# reaction_wheel_board.net
KiCad netlist of a schematic drawn in EAGLE
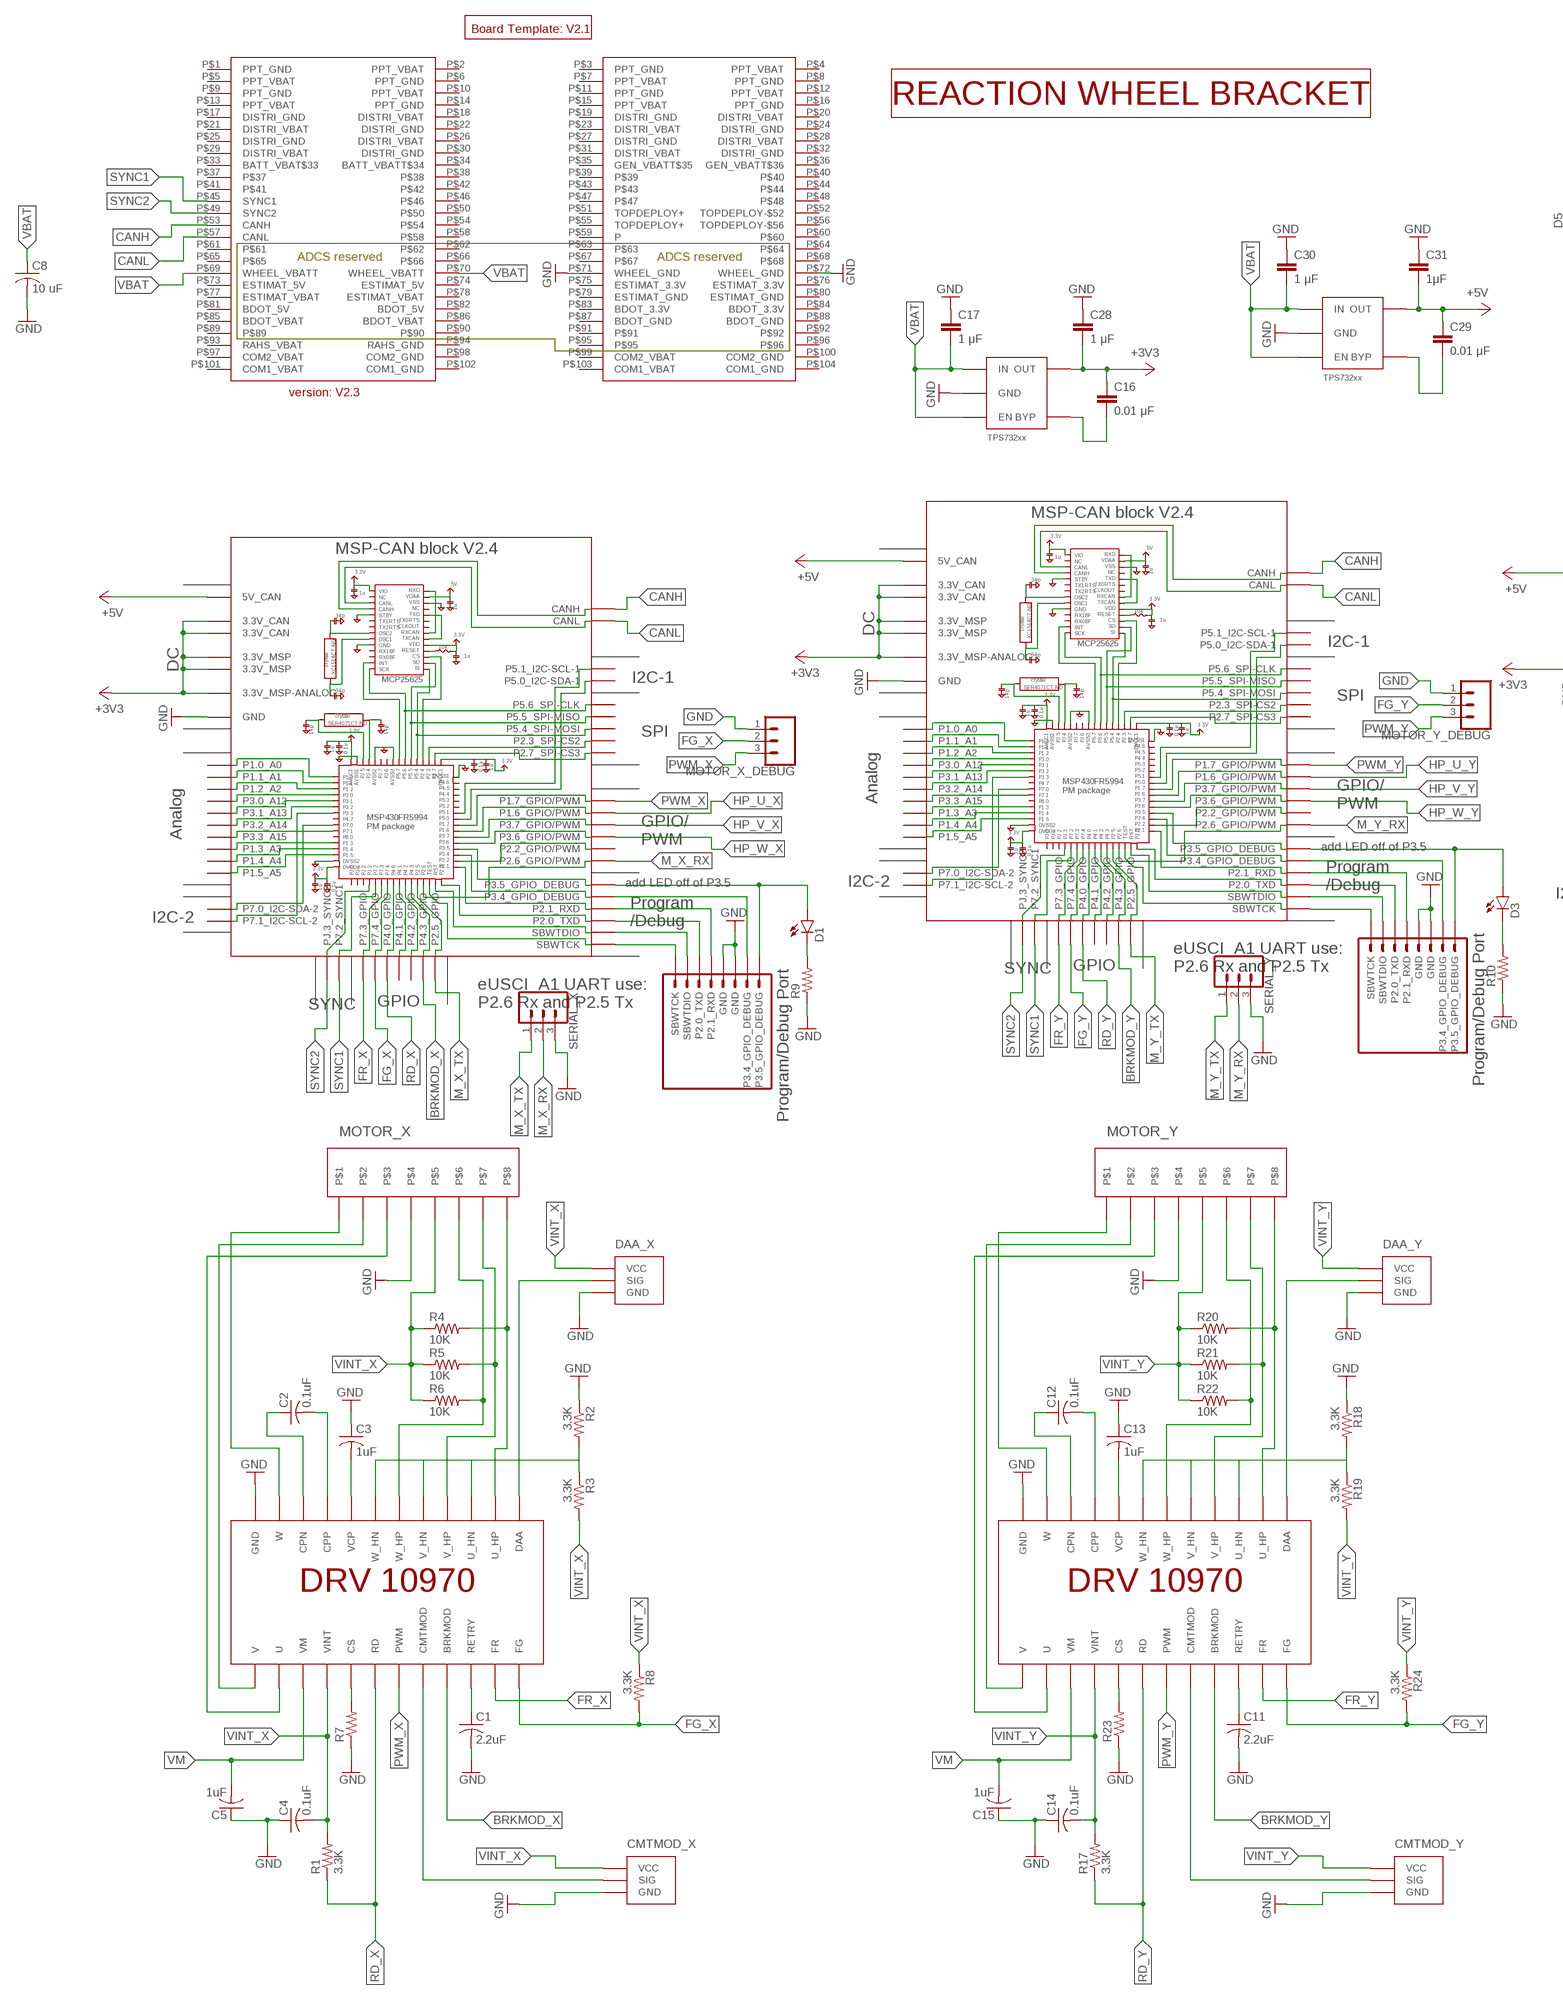
[diagram p0: schematic, sheet 1, part 1 of 2]
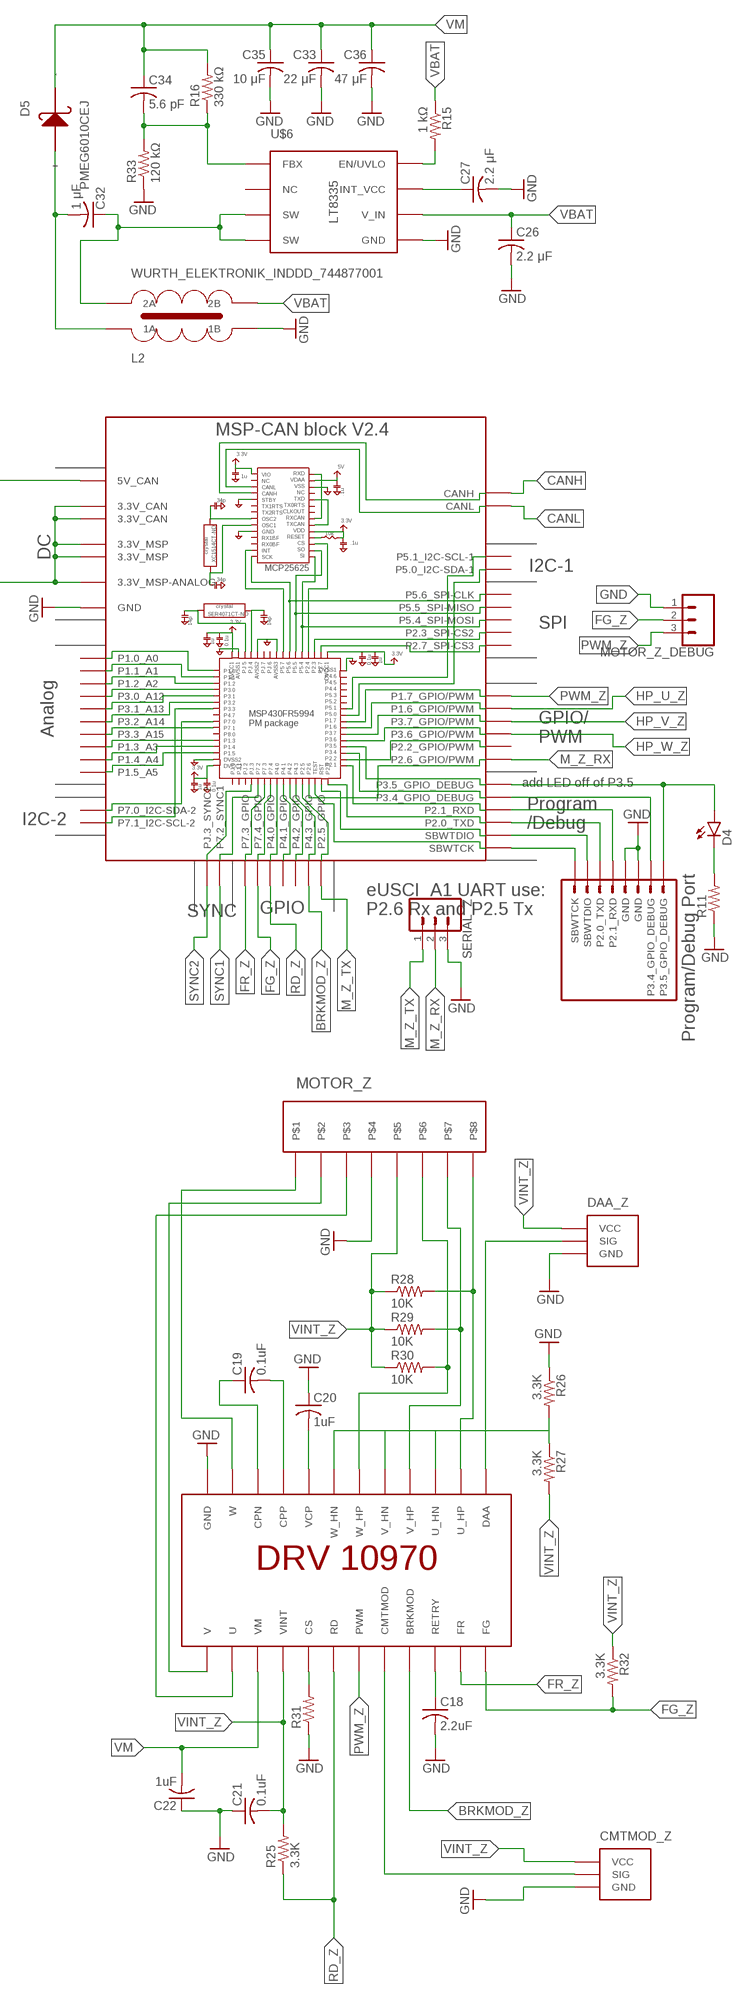
[diagram p1: schematic, sheet 1, part 2 of 2]

(export (version "E")
  (design (tool "Eeschema 10.0.6"))
  (components
    (comp (ref "C1")
      (value "2.2uF")
      (footprint "eagle-import:C1206")
      (libsource (lib "eagle-import") (part "C-USC1206"))
    )
    (comp (ref "C2")
      (value "0.1uF")
      (footprint "eagle-import:C0805")
      (libsource (lib "eagle-import") (part "C-USC0805"))
    )
    (comp (ref "C3")
      (value "1uF")
      (footprint "eagle-import:C1206")
      (libsource (lib "eagle-import") (part "C-USC1206"))
    )
    (comp (ref "C4")
      (value "0.1uF")
      (footprint "eagle-import:C0805")
      (libsource (lib "eagle-import") (part "C-USC0805"))
    )
    (comp (ref "C5")
      (value "1uF")
      (footprint "eagle-import:C1206")
      (libsource (lib "eagle-import") (part "C-USC1206"))
    )
    (comp (ref "C8")
      (value "10 uF")
      (footprint "eagle-import:C0805")
      (libsource (lib "eagle-import") (part "C-USC0805"))
    )
    (comp (ref "C11")
      (value "2.2uF")
      (footprint "eagle-import:C1206")
      (libsource (lib "eagle-import") (part "C-USC1206"))
    )
    (comp (ref "C12")
      (value "0.1uF")
      (footprint "eagle-import:C0805")
      (libsource (lib "eagle-import") (part "C-USC0805"))
    )
    (comp (ref "C13")
      (value "1uF")
      (footprint "eagle-import:C1206")
      (libsource (lib "eagle-import") (part "C-USC1206"))
    )
    (comp (ref "C14")
      (value "0.1uF")
      (footprint "eagle-import:C0805")
      (libsource (lib "eagle-import") (part "C-USC0805"))
    )
    (comp (ref "C15")
      (value "1uF")
      (footprint "eagle-import:C1206")
      (libsource (lib "eagle-import") (part "C-USC1206"))
    )
    (comp (ref "C16")
      (value "0.01 μF")
      (footprint "eagle-import:0805")
      (libsource (lib "eagle-import") (part "CAPACITOR0805"))
    )
    (comp (ref "C17")
      (value "1 μF")
      (footprint "eagle-import:0805")
      (libsource (lib "eagle-import") (part "CAPACITOR0805"))
    )
    (comp (ref "C18")
      (value "2.2uF")
      (footprint "eagle-import:C1206")
      (libsource (lib "eagle-import") (part "C-USC1206"))
    )
    (comp (ref "C19")
      (value "0.1uF")
      (footprint "eagle-import:C0805")
      (libsource (lib "eagle-import") (part "C-USC0805"))
    )
    (comp (ref "C20")
      (value "1uF")
      (footprint "eagle-import:C1206")
      (libsource (lib "eagle-import") (part "C-USC1206"))
    )
    (comp (ref "C21")
      (value "0.1uF")
      (footprint "eagle-import:C0805")
      (libsource (lib "eagle-import") (part "C-USC0805"))
    )
    (comp (ref "C22")
      (value "1uF")
      (footprint "eagle-import:C1206")
      (libsource (lib "eagle-import") (part "C-USC1206"))
    )
    (comp (ref "C26")
      (value "2.2 μF")
      (footprint "eagle-import:C0805")
      (libsource (lib "eagle-import") (part "C-USC0805"))
    )
    (comp (ref "C27")
      (value "2.2 μF")
      (footprint "eagle-import:C0805")
      (libsource (lib "eagle-import") (part "C-USC0805"))
    )
    (comp (ref "C28")
      (value "1 μF")
      (footprint "eagle-import:0805")
      (libsource (lib "eagle-import") (part "CAPACITOR0805"))
    )
    (comp (ref "C29")
      (value "0.01 μF")
      (footprint "eagle-import:0805")
      (libsource (lib "eagle-import") (part "CAPACITOR0805"))
    )
    (comp (ref "C30")
      (value "1 μF")
      (footprint "eagle-import:0805")
      (libsource (lib "eagle-import") (part "CAPACITOR0805"))
    )
    (comp (ref "C31")
      (value "1μF")
      (footprint "eagle-import:0805")
      (libsource (lib "eagle-import") (part "CAPACITOR0805"))
    )
    (comp (ref "C32")
      (value "1 μF")
      (footprint "eagle-import:C0805")
      (libsource (lib "eagle-import") (part "C-USC0805"))
    )
    (comp (ref "C33")
      (value "22 μF")
      (footprint "eagle-import:C1206")
      (libsource (lib "eagle-import") (part "C-USC1206"))
    )
    (comp (ref "C34")
      (value "5.6 pF")
      (footprint "eagle-import:C0805")
      (libsource (lib "eagle-import") (part "C-USC0805"))
    )
    (comp (ref "C35")
      (value "10 μF")
      (footprint "eagle-import:C0805")
      (libsource (lib "eagle-import") (part "C-USC0805"))
    )
    (comp (ref "C36")
      (value "47 μF")
      (footprint "eagle-import:C1206")
      (libsource (lib "eagle-import") (part "C-USC1206"))
    )
    (comp (ref "CMTMOD_X")
      (value "0_OHM_JUMPER")
      (footprint "eagle-import:0_OHM_JUMPER")
      (libsource (lib "eagle-import") (part "0_OHM_JUMPER"))
    )
    (comp (ref "CMTMOD_Y")
      (value "0_OHM_JUMPER")
      (footprint "eagle-import:0_OHM_JUMPER")
      (libsource (lib "eagle-import") (part "0_OHM_JUMPER"))
    )
    (comp (ref "CMTMOD_Z")
      (value "0_OHM_JUMPER")
      (footprint "eagle-import:0_OHM_JUMPER")
      (libsource (lib "eagle-import") (part "0_OHM_JUMPER"))
    )
    (comp (ref "D1")
      (value "LED")
      (footprint "eagle-import:LED-1206")
      (libsource (lib "eagle-import") (part "LED"))
    )
    (comp (ref "D3")
      (value "LED")
      (footprint "eagle-import:LED-1206")
      (libsource (lib "eagle-import") (part "LED"))
    )
    (comp (ref "D4")
      (value "LED")
      (footprint "eagle-import:LED-1206")
      (libsource (lib "eagle-import") (part "LED"))
    )
    (comp (ref "D5")
      (value "PMEG6010CEJ")
      (footprint "eagle-import:SC-90")
      (libsource (lib "eagle-import") (part "PMEG6010CEJ"))
    )
    (comp (ref "DAA_X")
      (value "0_OHM_JUMPER")
      (footprint "eagle-import:0_OHM_JUMPER")
      (libsource (lib "eagle-import") (part "0_OHM_JUMPER"))
    )
    (comp (ref "DAA_Y")
      (value "0_OHM_JUMPER")
      (footprint "eagle-import:0_OHM_JUMPER")
      (libsource (lib "eagle-import") (part "0_OHM_JUMPER"))
    )
    (comp (ref "DAA_Z")
      (value "0_OHM_JUMPER")
      (footprint "eagle-import:0_OHM_JUMPER")
      (libsource (lib "eagle-import") (part "0_OHM_JUMPER"))
    )
    (comp (ref "L2")
      (value "WURTH_ELEKTRONIK_INDDD_744877001")
      (footprint "eagle-import:WURTH_ELEKTRONIK_INDDD_744877001")
      (libsource (lib "eagle-import") (part "WURTH_ELEKTRONIK_INDDD_744877001"))
    )
    (comp (ref "MOTOR_X")
      (value "PICOLOCK_8")
      (footprint "eagle-import:PICOLOCK_8")
      (libsource (lib "eagle-import") (part "PICOLOCK_8"))
    )
    (comp (ref "MOTOR_X_DEBUG")
      (value "CONN_03LOCK")
      (footprint "eagle-import:1X03_LOCK")
      (libsource (lib "eagle-import") (part "CONN_03LOCK"))
    )
    (comp (ref "MOTOR_Y")
      (value "PICOLOCK_8")
      (footprint "eagle-import:PICOLOCK_8")
      (libsource (lib "eagle-import") (part "PICOLOCK_8"))
    )
    (comp (ref "MOTOR_Y_DEBUG")
      (value "CONN_03LOCK")
      (footprint "eagle-import:1X03_LOCK")
      (libsource (lib "eagle-import") (part "CONN_03LOCK"))
    )
    (comp (ref "MOTOR_Z")
      (value "PICOLOCK_8")
      (footprint "eagle-import:PICOLOCK_8")
      (libsource (lib "eagle-import") (part "PICOLOCK_8"))
    )
    (comp (ref "MOTOR_Z_DEBUG")
      (value "CONN_03LOCK")
      (footprint "eagle-import:1X03_LOCK")
      (libsource (lib "eagle-import") (part "CONN_03LOCK"))
    )
    (comp (ref "MSP_X_DEBUG")
      (value "PROGRAM/DEBUG_PORT")
      (footprint "eagle-import:1X08_CONNECTOR")
      (libsource (lib "eagle-import") (part "PROGRAM/DEBUG_PORT"))
    )
    (comp (ref "MSP_Y_DEBUG")
      (value "PROGRAM/DEBUG_PORT")
      (footprint "eagle-import:1X08_CONNECTOR")
      (libsource (lib "eagle-import") (part "PROGRAM/DEBUG_PORT"))
    )
    (comp (ref "MSP_Z_DEBUG")
      (value "PROGRAM/DEBUG_PORT")
      (footprint "eagle-import:1X08_CONNECTOR")
      (libsource (lib "eagle-import") (part "PROGRAM/DEBUG_PORT"))
    )
    (comp (ref "PC104")
      (value "PC104_CONNECTOR")
      (footprint "eagle-import:PC104_CONNECTOR")
      (libsource (lib "eagle-import") (part "PC104_CONNECTOR"))
    )
    (comp (ref "R1")
      (value "3.3K")
      (footprint "eagle-import:0805")
      (libsource (lib "eagle-import") (part "RESISTOR0805"))
    )
    (comp (ref "R2")
      (value "3.3K")
      (footprint "eagle-import:0805")
      (libsource (lib "eagle-import") (part "RESISTOR0805"))
    )
    (comp (ref "R3")
      (value "3.3K")
      (footprint "eagle-import:0805")
      (libsource (lib "eagle-import") (part "RESISTOR0805"))
    )
    (comp (ref "R4")
      (value "10K")
      (footprint "eagle-import:0805")
      (libsource (lib "eagle-import") (part "RESISTOR0805"))
    )
    (comp (ref "R5")
      (value "10K")
      (footprint "eagle-import:0805")
      (libsource (lib "eagle-import") (part "RESISTOR0805"))
    )
    (comp (ref "R6")
      (value "10K")
      (footprint "eagle-import:0805")
      (libsource (lib "eagle-import") (part "RESISTOR0805"))
    )
    (comp (ref "R7")
      (value "RESISTOR0805")
      (footprint "eagle-import:0805")
      (libsource (lib "eagle-import") (part "RESISTOR0805"))
    )
    (comp (ref "R8")
      (value "3.3K")
      (footprint "eagle-import:0805")
      (libsource (lib "eagle-import") (part "RESISTOR0805"))
    )
    (comp (ref "R9")
      (value "RESISTOR0805")
      (footprint "eagle-import:0805")
      (libsource (lib "eagle-import") (part "RESISTOR0805"))
    )
    (comp (ref "R10")
      (value "RESISTOR0805")
      (footprint "eagle-import:0805")
      (libsource (lib "eagle-import") (part "RESISTOR0805"))
    )
    (comp (ref "R11")
      (value "RESISTOR0805")
      (footprint "eagle-import:0805")
      (libsource (lib "eagle-import") (part "RESISTOR0805"))
    )
    (comp (ref "R15")
      (value "1 kΩ")
      (footprint "eagle-import:0805")
      (libsource (lib "eagle-import") (part "RESISTOR0805"))
    )
    (comp (ref "R16")
      (value "330 kΩ")
      (footprint "eagle-import:0805")
      (libsource (lib "eagle-import") (part "RESISTOR0805"))
    )
    (comp (ref "R17")
      (value "3.3K")
      (footprint "eagle-import:0805")
      (libsource (lib "eagle-import") (part "RESISTOR0805"))
    )
    (comp (ref "R18")
      (value "3.3K")
      (footprint "eagle-import:0805")
      (libsource (lib "eagle-import") (part "RESISTOR0805"))
    )
    (comp (ref "R19")
      (value "3.3K")
      (footprint "eagle-import:0805")
      (libsource (lib "eagle-import") (part "RESISTOR0805"))
    )
    (comp (ref "R20")
      (value "10K")
      (footprint "eagle-import:0805")
      (libsource (lib "eagle-import") (part "RESISTOR0805"))
    )
    (comp (ref "R21")
      (value "10K")
      (footprint "eagle-import:0805")
      (libsource (lib "eagle-import") (part "RESISTOR0805"))
    )
    (comp (ref "R22")
      (value "10K")
      (footprint "eagle-import:0805")
      (libsource (lib "eagle-import") (part "RESISTOR0805"))
    )
    (comp (ref "R23")
      (value "RESISTOR0805")
      (footprint "eagle-import:0805")
      (libsource (lib "eagle-import") (part "RESISTOR0805"))
    )
    (comp (ref "R24")
      (value "3.3K")
      (footprint "eagle-import:0805")
      (libsource (lib "eagle-import") (part "RESISTOR0805"))
    )
    (comp (ref "R25")
      (value "3.3K")
      (footprint "eagle-import:0805")
      (libsource (lib "eagle-import") (part "RESISTOR0805"))
    )
    (comp (ref "R26")
      (value "3.3K")
      (footprint "eagle-import:0805")
      (libsource (lib "eagle-import") (part "RESISTOR0805"))
    )
    (comp (ref "R27")
      (value "3.3K")
      (footprint "eagle-import:0805")
      (libsource (lib "eagle-import") (part "RESISTOR0805"))
    )
    (comp (ref "R28")
      (value "10K")
      (footprint "eagle-import:0805")
      (libsource (lib "eagle-import") (part "RESISTOR0805"))
    )
    (comp (ref "R29")
      (value "10K")
      (footprint "eagle-import:0805")
      (libsource (lib "eagle-import") (part "RESISTOR0805"))
    )
    (comp (ref "R30")
      (value "10K")
      (footprint "eagle-import:0805")
      (libsource (lib "eagle-import") (part "RESISTOR0805"))
    )
    (comp (ref "R31")
      (value "RESISTOR0805")
      (footprint "eagle-import:0805")
      (libsource (lib "eagle-import") (part "RESISTOR0805"))
    )
    (comp (ref "R32")
      (value "3.3K")
      (footprint "eagle-import:0805")
      (libsource (lib "eagle-import") (part "RESISTOR0805"))
    )
    (comp (ref "R33")
      (value "120 kΩ")
      (footprint "eagle-import:0805")
      (libsource (lib "eagle-import") (part "RESISTOR0805"))
    )
    (comp (ref "SERIAL_X")
      (value "CONN_03LOCK")
      (footprint "eagle-import:1X03_LOCK")
      (libsource (lib "eagle-import") (part "CONN_03LOCK"))
    )
    (comp (ref "SERIAL_Y")
      (value "CONN_03LOCK")
      (footprint "eagle-import:1X03_LOCK")
      (libsource (lib "eagle-import") (part "CONN_03LOCK"))
    )
    (comp (ref "SERIAL_Z")
      (value "CONN_03LOCK")
      (footprint "eagle-import:1X03_LOCK")
      (libsource (lib "eagle-import") (part "CONN_03LOCK"))
    )
    (comp (ref "U$1")
      (value "BOARD_TEMPLATESERCURED")
      (footprint "eagle-import:BOARD_TEMPLATE_SECURED")
      (libsource (lib "eagle-import") (part "BOARD_TEMPLATESERCURED"))
    )
    (comp (ref "U$3")
      (value "MSP-CAN_BLOCK")
      (footprint "eagle-import:MSP-CAN_BLOCK")
      (libsource (lib "eagle-import") (part "MSP-CAN_BLOCK"))
    )
    (comp (ref "U$6")
      (value "LT8335")
      (footprint "eagle-import:DDB")
      (libsource (lib "eagle-import") (part "LT8335"))
    )
    (comp (ref "U$7")
      (value "DRV10970")
      (footprint "eagle-import:DRV10970")
      (libsource (lib "eagle-import") (part "DRV10970"))
    )
    (comp (ref "U$9")
      (value "REACTION_WHEEL_BRACKET")
      (footprint "eagle-import:REACTION_WHEEL_BRACKET")
      (libsource (lib "eagle-import") (part "REACTION_WHEEL_BRACKET"))
    )
    (comp (ref "U$10")
      (value "MSP-CAN_BLOCK")
      (footprint "eagle-import:MSP-CAN_BLOCK")
      (libsource (lib "eagle-import") (part "MSP-CAN_BLOCK"))
    )
    (comp (ref "U$12")
      (value "DRV10970")
      (footprint "eagle-import:DRV10970")
      (libsource (lib "eagle-import") (part "DRV10970"))
    )
    (comp (ref "U$13")
      (value "MSP-CAN_BLOCK")
      (footprint "eagle-import:MSP-CAN_BLOCK")
      (libsource (lib "eagle-import") (part "MSP-CAN_BLOCK"))
    )
    (comp (ref "U$15")
      (value "DRV10970")
      (footprint "eagle-import:DRV10970")
      (libsource (lib "eagle-import") (part "DRV10970"))
    )
    (comp (ref "U2")
      (value "TPS732XX")
      (footprint "eagle-import:SOT-23-5")
      (libsource (lib "eagle-import") (part "TPS732XX"))
    )
    (comp (ref "U3")
      (value "TPS732XX")
      (footprint "eagle-import:SOT-23-5")
      (libsource (lib "eagle-import") (part "TPS732XX"))
    )
  )
  (nets
    (net (code "1") (name "+3V3") (class "Default")
      (node (ref "C16") (pin "1") (pinfunction "1_1") (pintype "passive"))
      (node (ref "C28") (pin "2") (pinfunction "2_2") (pintype "passive"))
      (node (ref "U$10") (pin "3.3V@CAN1") (pinfunction "3.3V_CAN_3.3V@CAN1") (pintype "bidirectional"))
      (node (ref "U$10") (pin "3.3V@CAN2") (pinfunction "3.3V_CAN_3.3V@CAN2") (pintype "bidirectional"))
      (node (ref "U$10") (pin "3.3V@MSP1") (pinfunction "3.3V_MSP_3.3V@MSP1") (pintype "bidirectional"))
      (node (ref "U$10") (pin "3.3V@MSP2") (pinfunction "3.3V_MSP_3.3V@MSP2") (pintype "bidirectional"))
      (node (ref "U$10") (pin "3.3V_ANALOG@MSP2") (pinfunction "3.3V_MSP-ANALOG_3.3V_ANALOG@MSP2") (pintype "bidirectional"))
      (node (ref "U$13") (pin "3.3V@CAN1") (pinfunction "3.3V_CAN_3.3V@CAN1") (pintype "bidirectional"))
      (node (ref "U$13") (pin "3.3V@CAN2") (pinfunction "3.3V_CAN_3.3V@CAN2") (pintype "bidirectional"))
      (node (ref "U$13") (pin "3.3V@MSP1") (pinfunction "3.3V_MSP_3.3V@MSP1") (pintype "bidirectional"))
      (node (ref "U$13") (pin "3.3V@MSP2") (pinfunction "3.3V_MSP_3.3V@MSP2") (pintype "bidirectional"))
      (node (ref "U$13") (pin "3.3V_ANALOG@MSP2") (pinfunction "3.3V_MSP-ANALOG_3.3V_ANALOG@MSP2") (pintype "bidirectional"))
      (node (ref "U$3") (pin "3.3V@CAN1") (pinfunction "3.3V_CAN_3.3V@CAN1") (pintype "bidirectional"))
      (node (ref "U$3") (pin "3.3V@CAN2") (pinfunction "3.3V_CAN_3.3V@CAN2") (pintype "bidirectional"))
      (node (ref "U$3") (pin "3.3V@MSP1") (pinfunction "3.3V_MSP_3.3V@MSP1") (pintype "bidirectional"))
      (node (ref "U$3") (pin "3.3V@MSP2") (pinfunction "3.3V_MSP_3.3V@MSP2") (pintype "bidirectional"))
      (node (ref "U$3") (pin "3.3V_ANALOG@MSP2") (pinfunction "3.3V_MSP-ANALOG_3.3V_ANALOG@MSP2") (pintype "bidirectional"))
      (node (ref "U2") (pin "P$5") (pinfunction "OUT_P$5") (pintype "bidirectional"))
    )
    (net (code "2") (name "+5V") (class "Default")
      (node (ref "C29") (pin "1") (pinfunction "1_1") (pintype "passive"))
      (node (ref "C31") (pin "2") (pinfunction "2_2") (pintype "passive"))
      (node (ref "U$10") (pin "5V") (pinfunction "5V_CAN_5V") (pintype "bidirectional"))
      (node (ref "U$13") (pin "5V") (pinfunction "5V_CAN_5V") (pintype "bidirectional"))
      (node (ref "U$3") (pin "5V") (pinfunction "5V_CAN_5V") (pintype "bidirectional"))
      (node (ref "U3") (pin "P$5") (pinfunction "OUT_P$5") (pintype "bidirectional"))
    )
    (net (code "3") (name "BRKMOD_X") (class "Default")
      (node (ref "U$3") (pin "P4.3_GPIO") (pinfunction "P4.3_GPIO_P4.3_GPIO") (pintype "bidirectional"))
      (node (ref "U$7") (pin "BRKMOD") (pinfunction "BRKMOD_BRKMOD") (pintype "bidirectional"))
    )
    (net (code "4") (name "BRKMOD_Y") (class "Default")
      (node (ref "U$10") (pin "P4.3_GPIO") (pinfunction "P4.3_GPIO_P4.3_GPIO") (pintype "bidirectional"))
      (node (ref "U$12") (pin "BRKMOD") (pinfunction "BRKMOD_BRKMOD") (pintype "bidirectional"))
    )
    (net (code "5") (name "BRKMOD_Z") (class "Default")
      (node (ref "U$13") (pin "P4.3_GPIO") (pinfunction "P4.3_GPIO_P4.3_GPIO") (pintype "bidirectional"))
      (node (ref "U$15") (pin "BRKMOD") (pinfunction "BRKMOD_BRKMOD") (pintype "bidirectional"))
    )
    (net (code "6") (name "CANH") (class "Default")
      (node (ref "PC104") (pin "P$53") (pinfunction "CANH_P$53") (pintype "bidirectional"))
      (node (ref "U$10") (pin "CANH") (pinfunction "CANH_CANH") (pintype "bidirectional"))
      (node (ref "U$13") (pin "CANH") (pinfunction "CANH_CANH") (pintype "bidirectional"))
      (node (ref "U$3") (pin "CANH") (pinfunction "CANH_CANH") (pintype "bidirectional"))
    )
    (net (code "7") (name "CANL") (class "Default")
      (node (ref "PC104") (pin "P$57") (pinfunction "CANL_P$57") (pintype "bidirectional"))
      (node (ref "U$10") (pin "CANL") (pinfunction "CANL_CANL") (pintype "bidirectional"))
      (node (ref "U$13") (pin "CANL") (pinfunction "CANL_CANL") (pintype "bidirectional"))
      (node (ref "U$3") (pin "CANL") (pinfunction "CANL_CANL") (pintype "bidirectional"))
    )
    (net (code "8") (name "FG_X") (class "Default")
      (node (ref "MOTOR_X_DEBUG") (pin "2") (pinfunction "2_2") (pintype "passive"))
      (node (ref "R8") (pin "2") (pinfunction "2_2") (pintype "passive"))
      (node (ref "U$3") (pin "P7.4_GPIO") (pinfunction "P7.4_GPIO_P7.4_GPIO") (pintype "bidirectional"))
      (node (ref "U$7") (pin "FG") (pinfunction "FG_FG") (pintype "bidirectional"))
    )
    (net (code "9") (name "FG_Y") (class "Default")
      (node (ref "MOTOR_Y_DEBUG") (pin "2") (pinfunction "2_2") (pintype "passive"))
      (node (ref "R24") (pin "2") (pinfunction "2_2") (pintype "passive"))
      (node (ref "U$10") (pin "P7.4_GPIO") (pinfunction "P7.4_GPIO_P7.4_GPIO") (pintype "bidirectional"))
      (node (ref "U$12") (pin "FG") (pinfunction "FG_FG") (pintype "bidirectional"))
    )
    (net (code "10") (name "FG_Z") (class "Default")
      (node (ref "MOTOR_Z_DEBUG") (pin "2") (pinfunction "2_2") (pintype "passive"))
      (node (ref "R32") (pin "2") (pinfunction "2_2") (pintype "passive"))
      (node (ref "U$13") (pin "P7.4_GPIO") (pinfunction "P7.4_GPIO_P7.4_GPIO") (pintype "bidirectional"))
      (node (ref "U$15") (pin "FG") (pinfunction "FG_FG") (pintype "bidirectional"))
    )
    (net (code "11") (name "FR_X") (class "Default")
      (node (ref "U$3") (pin "P7.3_GPIO") (pinfunction "P7.3_GPIO_P7.3_GPIO") (pintype "bidirectional"))
      (node (ref "U$7") (pin "FR") (pinfunction "FR_FR") (pintype "bidirectional"))
    )
    (net (code "12") (name "FR_Y") (class "Default")
      (node (ref "U$10") (pin "P7.3_GPIO") (pinfunction "P7.3_GPIO_P7.3_GPIO") (pintype "bidirectional"))
      (node (ref "U$12") (pin "FR") (pinfunction "FR_FR") (pintype "bidirectional"))
    )
    (net (code "13") (name "FR_Z") (class "Default")
      (node (ref "U$13") (pin "P7.3_GPIO") (pinfunction "P7.3_GPIO_P7.3_GPIO") (pintype "bidirectional"))
      (node (ref "U$15") (pin "FR") (pinfunction "FR_FR") (pintype "bidirectional"))
    )
    (net (code "14") (name "GND") (class "Default")
      (node (ref "C1") (pin "2") (pinfunction "2_2") (pintype "passive"))
      (node (ref "C11") (pin "2") (pinfunction "2_2") (pintype "passive"))
      (node (ref "C13") (pin "1") (pinfunction "1_1") (pintype "passive"))
      (node (ref "C14") (pin "1") (pinfunction "1_1") (pintype "passive"))
      (node (ref "C15") (pin "1") (pinfunction "1_1") (pintype "passive"))
      (node (ref "C17") (pin "1") (pinfunction "1_1") (pintype "passive"))
      (node (ref "C18") (pin "2") (pinfunction "2_2") (pintype "passive"))
      (node (ref "C20") (pin "1") (pinfunction "1_1") (pintype "passive"))
      (node (ref "C21") (pin "1") (pinfunction "1_1") (pintype "passive"))
      (node (ref "C22") (pin "1") (pinfunction "1_1") (pintype "passive"))
      (node (ref "C26") (pin "2") (pinfunction "2_2") (pintype "passive"))
      (node (ref "C27") (pin "2") (pinfunction "2_2") (pintype "passive"))
      (node (ref "C28") (pin "1") (pinfunction "1_1") (pintype "passive"))
      (node (ref "C3") (pin "1") (pinfunction "1_1") (pintype "passive"))
      (node (ref "C30") (pin "1") (pinfunction "1_1") (pintype "passive"))
      (node (ref "C31") (pin "1") (pinfunction "1_1") (pintype "passive"))
      (node (ref "C33") (pin "2") (pinfunction "2_2") (pintype "passive"))
      (node (ref "C35") (pin "2") (pinfunction "2_2") (pintype "passive"))
      (node (ref "C36") (pin "2") (pinfunction "2_2") (pintype "passive"))
      (node (ref "C4") (pin "1") (pinfunction "1_1") (pintype "passive"))
      (node (ref "C5") (pin "1") (pinfunction "1_1") (pintype "passive"))
      (node (ref "C8") (pin "2") (pinfunction "2_2") (pintype "passive"))
      (node (ref "CMTMOD_X") (pin "P$1") (pinfunction "GND_P$1") (pintype "bidirectional"))
      (node (ref "CMTMOD_Y") (pin "P$1") (pinfunction "GND_P$1") (pintype "bidirectional"))
      (node (ref "CMTMOD_Z") (pin "P$1") (pinfunction "GND_P$1") (pintype "bidirectional"))
      (node (ref "DAA_X") (pin "P$1") (pinfunction "GND_P$1") (pintype "bidirectional"))
      (node (ref "DAA_Y") (pin "P$1") (pinfunction "GND_P$1") (pintype "bidirectional"))
      (node (ref "DAA_Z") (pin "P$1") (pinfunction "GND_P$1") (pintype "bidirectional"))
      (node (ref "L2") (pin "P$2") (pinfunction "1B_P$2") (pintype "bidirectional"))
      (node (ref "MOTOR_X") (pin "P$4") (pinfunction "P$4_P$4") (pintype "bidirectional"))
      (node (ref "MOTOR_X_DEBUG") (pin "1") (pinfunction "1_1") (pintype "passive"))
      (node (ref "MOTOR_Y") (pin "P$4") (pinfunction "P$4_P$4") (pintype "bidirectional"))
      (node (ref "MOTOR_Y_DEBUG") (pin "1") (pinfunction "1_1") (pintype "passive"))
      (node (ref "MOTOR_Z") (pin "P$4") (pinfunction "P$4_P$4") (pintype "bidirectional"))
      (node (ref "MOTOR_Z_DEBUG") (pin "1") (pinfunction "1_1") (pintype "passive"))
      (node (ref "MSP_X_DEBUG") (pin "5") (pinfunction "GND_5") (pintype "bidirectional"))
      (node (ref "MSP_X_DEBUG") (pin "6") (pinfunction "GND_6") (pintype "bidirectional"))
      (node (ref "MSP_Y_DEBUG") (pin "5") (pinfunction "GND_5") (pintype "bidirectional"))
      (node (ref "MSP_Y_DEBUG") (pin "6") (pinfunction "GND_6") (pintype "bidirectional"))
      (node (ref "MSP_Z_DEBUG") (pin "5") (pinfunction "GND_5") (pintype "bidirectional"))
      (node (ref "MSP_Z_DEBUG") (pin "6") (pinfunction "GND_6") (pintype "bidirectional"))
      (node (ref "PC104") (pin "P$71") (pinfunction "WHEEL_GND_P$71") (pintype "bidirectional"))
      (node (ref "PC104") (pin "P$72") (pinfunction "WHEEL_GND_P$72") (pintype "bidirectional"))
      (node (ref "R10") (pin "1") (pinfunction "1_1") (pintype "passive"))
      (node (ref "R11") (pin "1") (pinfunction "1_1") (pintype "passive"))
      (node (ref "R18") (pin "1") (pinfunction "1_1") (pintype "passive"))
      (node (ref "R2") (pin "1") (pinfunction "1_1") (pintype "passive"))
      (node (ref "R23") (pin "1") (pinfunction "1_1") (pintype "passive"))
      (node (ref "R26") (pin "1") (pinfunction "1_1") (pintype "passive"))
      (node (ref "R31") (pin "1") (pinfunction "1_1") (pintype "passive"))
      (node (ref "R33") (pin "1") (pinfunction "1_1") (pintype "passive"))
      (node (ref "R7") (pin "1") (pinfunction "1_1") (pintype "passive"))
      (node (ref "R9") (pin "1") (pinfunction "1_1") (pintype "passive"))
      (node (ref "SERIAL_X") (pin "3") (pinfunction "3_3") (pintype "passive"))
      (node (ref "SERIAL_Y") (pin "3") (pinfunction "3_3") (pintype "passive"))
      (node (ref "SERIAL_Z") (pin "3") (pinfunction "3_3") (pintype "passive"))
      (node (ref "U$10") (pin "GND@1") (pinfunction "GND_GND@1") (pintype "bidirectional"))
      (node (ref "U$10") (pin "GND@10") (pinfunction "GND_GND@10") (pintype "bidirectional"))
      (node (ref "U$10") (pin "GND@11") (pinfunction "GND_GND@11") (pintype "bidirectional"))
      (node (ref "U$10") (pin "GND@12") (pinfunction "GND_GND@12") (pintype "bidirectional"))
      (node (ref "U$10") (pin "GND@13") (pinfunction "GND_GND@13") (pintype "bidirectional"))
      (node (ref "U$10") (pin "GND@14") (pinfunction "GND_GND@14") (pintype "bidirectional"))
      (node (ref "U$10") (pin "GND@15") (pinfunction "GND_GND@15") (pintype "bidirectional"))
      (node (ref "U$10") (pin "GND@16") (pinfunction "GND_GND@16") (pintype "bidirectional"))
      (node (ref "U$10") (pin "GND@17") (pinfunction "GND_GND@17") (pintype "bidirectional"))
      (node (ref "U$10") (pin "GND@2") (pinfunction "GND_GND@2") (pintype "bidirectional"))
      (node (ref "U$10") (pin "GND@26") (pinfunction "GND_GND@26") (pintype "bidirectional"))
      (node (ref "U$10") (pin "GND@3") (pinfunction "GND_GND@3") (pintype "bidirectional"))
      (node (ref "U$10") (pin "GND@4") (pinfunction "GND_GND@4") (pintype "bidirectional"))
      (node (ref "U$10") (pin "GND@5") (pinfunction "GND_GND@5") (pintype "bidirectional"))
      (node (ref "U$10") (pin "GND@7") (pinfunction "GND_GND@7") (pintype "bidirectional"))
      (node (ref "U$10") (pin "GND@8") (pinfunction "GND_GND@8") (pintype "bidirectional"))
      (node (ref "U$10") (pin "GND@9") (pinfunction "GND_GND@9") (pintype "bidirectional"))
      (node (ref "U$12") (pin "GND@1") (pinfunction "GND_GND@1") (pintype "bidirectional"))
      (node (ref "U$12") (pin "GND@2") (pinfunction "GND_GND@2") (pintype "bidirectional"))
      (node (ref "U$13") (pin "GND@1") (pinfunction "GND_GND@1") (pintype "bidirectional"))
      (node (ref "U$13") (pin "GND@10") (pinfunction "GND_GND@10") (pintype "bidirectional"))
      (node (ref "U$13") (pin "GND@11") (pinfunction "GND_GND@11") (pintype "bidirectional"))
      (node (ref "U$13") (pin "GND@12") (pinfunction "GND_GND@12") (pintype "bidirectional"))
      (node (ref "U$13") (pin "GND@13") (pinfunction "GND_GND@13") (pintype "bidirectional"))
      (node (ref "U$13") (pin "GND@14") (pinfunction "GND_GND@14") (pintype "bidirectional"))
      (node (ref "U$13") (pin "GND@15") (pinfunction "GND_GND@15") (pintype "bidirectional"))
      (node (ref "U$13") (pin "GND@16") (pinfunction "GND_GND@16") (pintype "bidirectional"))
      (node (ref "U$13") (pin "GND@17") (pinfunction "GND_GND@17") (pintype "bidirectional"))
      (node (ref "U$13") (pin "GND@2") (pinfunction "GND_GND@2") (pintype "bidirectional"))
      (node (ref "U$13") (pin "GND@26") (pinfunction "GND_GND@26") (pintype "bidirectional"))
      (node (ref "U$13") (pin "GND@3") (pinfunction "GND_GND@3") (pintype "bidirectional"))
      (node (ref "U$13") (pin "GND@4") (pinfunction "GND_GND@4") (pintype "bidirectional"))
      (node (ref "U$13") (pin "GND@5") (pinfunction "GND_GND@5") (pintype "bidirectional"))
      (node (ref "U$13") (pin "GND@7") (pinfunction "GND_GND@7") (pintype "bidirectional"))
      (node (ref "U$13") (pin "GND@8") (pinfunction "GND_GND@8") (pintype "bidirectional"))
      (node (ref "U$13") (pin "GND@9") (pinfunction "GND_GND@9") (pintype "bidirectional"))
      (node (ref "U$15") (pin "GND@1") (pinfunction "GND_GND@1") (pintype "bidirectional"))
      (node (ref "U$15") (pin "GND@2") (pinfunction "GND_GND@2") (pintype "bidirectional"))
      (node (ref "U$3") (pin "GND@1") (pinfunction "GND_GND@1") (pintype "bidirectional"))
      (node (ref "U$3") (pin "GND@10") (pinfunction "GND_GND@10") (pintype "bidirectional"))
      (node (ref "U$3") (pin "GND@11") (pinfunction "GND_GND@11") (pintype "bidirectional"))
      (node (ref "U$3") (pin "GND@12") (pinfunction "GND_GND@12") (pintype "bidirectional"))
      (node (ref "U$3") (pin "GND@13") (pinfunction "GND_GND@13") (pintype "bidirectional"))
      (node (ref "U$3") (pin "GND@14") (pinfunction "GND_GND@14") (pintype "bidirectional"))
      (node (ref "U$3") (pin "GND@15") (pinfunction "GND_GND@15") (pintype "bidirectional"))
      (node (ref "U$3") (pin "GND@16") (pinfunction "GND_GND@16") (pintype "bidirectional"))
      (node (ref "U$3") (pin "GND@17") (pinfunction "GND_GND@17") (pintype "bidirectional"))
      (node (ref "U$3") (pin "GND@2") (pinfunction "GND_GND@2") (pintype "bidirectional"))
      (node (ref "U$3") (pin "GND@26") (pinfunction "GND_GND@26") (pintype "bidirectional"))
      (node (ref "U$3") (pin "GND@3") (pinfunction "GND_GND@3") (pintype "bidirectional"))
      (node (ref "U$3") (pin "GND@4") (pinfunction "GND_GND@4") (pintype "bidirectional"))
      (node (ref "U$3") (pin "GND@5") (pinfunction "GND_GND@5") (pintype "bidirectional"))
      (node (ref "U$3") (pin "GND@7") (pinfunction "GND_GND@7") (pintype "bidirectional"))
      (node (ref "U$3") (pin "GND@8") (pinfunction "GND_GND@8") (pintype "bidirectional"))
      (node (ref "U$3") (pin "GND@9") (pinfunction "GND_GND@9") (pintype "bidirectional"))
      (node (ref "U$6") (pin "GND") (pinfunction "GND_GND") (pintype "bidirectional"))
      (node (ref "U$6") (pin "P$5") (pinfunction "GND_P$5") (pintype "bidirectional"))
      (node (ref "U$7") (pin "GND@1") (pinfunction "GND_GND@1") (pintype "bidirectional"))
      (node (ref "U$7") (pin "GND@2") (pinfunction "GND_GND@2") (pintype "bidirectional"))
      (node (ref "U2") (pin "P$2") (pinfunction "GND_P$2") (pintype "bidirectional"))
      (node (ref "U3") (pin "P$2") (pinfunction "GND_P$2") (pintype "bidirectional"))
    )
    (net (code "15") (name "HP_U_X") (class "Default")
      (node (ref "MOTOR_X") (pin "P$8") (pinfunction "P$8_P$8") (pintype "bidirectional"))
      (node (ref "R4") (pin "2") (pinfunction "2_2") (pintype "passive"))
      (node (ref "U$3") (pin "P1.6_GPIO/PWM") (pinfunction "P1.6_GPIO/PWM_P1.6_GPIO/PWM") (pintype "bidirectional"))
      (node (ref "U$7") (pin "U_HP") (pinfunction "U_HP_U_HP") (pintype "bidirectional"))
    )
    (net (code "16") (name "HP_U_Y") (class "Default")
      (node (ref "MOTOR_Y") (pin "P$8") (pinfunction "P$8_P$8") (pintype "bidirectional"))
      (node (ref "R20") (pin "2") (pinfunction "2_2") (pintype "passive"))
      (node (ref "U$10") (pin "P1.6_GPIO/PWM") (pinfunction "P1.6_GPIO/PWM_P1.6_GPIO/PWM") (pintype "bidirectional"))
      (node (ref "U$12") (pin "U_HP") (pinfunction "U_HP_U_HP") (pintype "bidirectional"))
    )
    (net (code "17") (name "HP_U_Z") (class "Default")
      (node (ref "MOTOR_Z") (pin "P$8") (pinfunction "P$8_P$8") (pintype "bidirectional"))
      (node (ref "R28") (pin "2") (pinfunction "2_2") (pintype "passive"))
      (node (ref "U$13") (pin "P1.6_GPIO/PWM") (pinfunction "P1.6_GPIO/PWM_P1.6_GPIO/PWM") (pintype "bidirectional"))
      (node (ref "U$15") (pin "U_HP") (pinfunction "U_HP_U_HP") (pintype "bidirectional"))
    )
    (net (code "18") (name "HP_V_X") (class "Default")
      (node (ref "MOTOR_X") (pin "P$7") (pinfunction "P$7_P$7") (pintype "bidirectional"))
      (node (ref "R5") (pin "2") (pinfunction "2_2") (pintype "passive"))
      (node (ref "U$3") (pin "P3.7_GPIO/PWM") (pinfunction "P3.7_GPIO/PWM_P3.7_GPIO/PWM") (pintype "bidirectional"))
      (node (ref "U$7") (pin "V_HP") (pinfunction "V_HP_V_HP") (pintype "bidirectional"))
    )
    (net (code "19") (name "HP_V_Y") (class "Default")
      (node (ref "MOTOR_Y") (pin "P$7") (pinfunction "P$7_P$7") (pintype "bidirectional"))
      (node (ref "R21") (pin "2") (pinfunction "2_2") (pintype "passive"))
      (node (ref "U$10") (pin "P3.7_GPIO/PWM") (pinfunction "P3.7_GPIO/PWM_P3.7_GPIO/PWM") (pintype "bidirectional"))
      (node (ref "U$12") (pin "V_HP") (pinfunction "V_HP_V_HP") (pintype "bidirectional"))
    )
    (net (code "20") (name "HP_V_Z") (class "Default")
      (node (ref "MOTOR_Z") (pin "P$7") (pinfunction "P$7_P$7") (pintype "bidirectional"))
      (node (ref "R29") (pin "2") (pinfunction "2_2") (pintype "passive"))
      (node (ref "U$13") (pin "P3.7_GPIO/PWM") (pinfunction "P3.7_GPIO/PWM_P3.7_GPIO/PWM") (pintype "bidirectional"))
      (node (ref "U$15") (pin "V_HP") (pinfunction "V_HP_V_HP") (pintype "bidirectional"))
    )
    (net (code "21") (name "HP_W_X") (class "Default")
      (node (ref "MOTOR_X") (pin "P$6") (pinfunction "P$6_P$6") (pintype "bidirectional"))
      (node (ref "R6") (pin "2") (pinfunction "2_2") (pintype "passive"))
      (node (ref "U$3") (pin "P3.6_GPIO/PWM") (pinfunction "P3.6_GPIO/PWM_P3.6_GPIO/PWM") (pintype "bidirectional"))
      (node (ref "U$7") (pin "W_HP") (pinfunction "W_HP_W_HP") (pintype "bidirectional"))
    )
    (net (code "22") (name "HP_W_Y") (class "Default")
      (node (ref "MOTOR_Y") (pin "P$6") (pinfunction "P$6_P$6") (pintype "bidirectional"))
      (node (ref "R22") (pin "2") (pinfunction "2_2") (pintype "passive"))
      (node (ref "U$10") (pin "P3.6_GPIO/PWM") (pinfunction "P3.6_GPIO/PWM_P3.6_GPIO/PWM") (pintype "bidirectional"))
      (node (ref "U$12") (pin "W_HP") (pinfunction "W_HP_W_HP") (pintype "bidirectional"))
    )
    (net (code "23") (name "HP_W_Z") (class "Default")
      (node (ref "MOTOR_Z") (pin "P$6") (pinfunction "P$6_P$6") (pintype "bidirectional"))
      (node (ref "R30") (pin "2") (pinfunction "2_2") (pintype "passive"))
      (node (ref "U$13") (pin "P3.6_GPIO/PWM") (pinfunction "P3.6_GPIO/PWM_P3.6_GPIO/PWM") (pintype "bidirectional"))
      (node (ref "U$15") (pin "W_HP") (pinfunction "W_HP_W_HP") (pintype "bidirectional"))
    )
    (net (code "24") (name "M_X_RX") (class "Default")
      (node (ref "SERIAL_X") (pin "2") (pinfunction "2_2") (pintype "passive"))
      (node (ref "U$3") (pin "P2.6_GPIO/PWM") (pinfunction "P2.6_GPIO/PWM_P2.6_GPIO/PWM") (pintype "bidirectional"))
    )
    (net (code "25") (name "M_X_TX") (class "Default")
      (node (ref "SERIAL_X") (pin "1") (pinfunction "1_1") (pintype "passive"))
      (node (ref "U$3") (pin "P2.5_GPIO") (pinfunction "P2.5_GPIO_P2.5_GPIO") (pintype "bidirectional"))
    )
    (net (code "26") (name "M_Y_RX") (class "Default")
      (node (ref "SERIAL_Y") (pin "2") (pinfunction "2_2") (pintype "passive"))
      (node (ref "U$10") (pin "P2.6_GPIO/PWM") (pinfunction "P2.6_GPIO/PWM_P2.6_GPIO/PWM") (pintype "bidirectional"))
    )
    (net (code "27") (name "M_Y_TX") (class "Default")
      (node (ref "SERIAL_Y") (pin "1") (pinfunction "1_1") (pintype "passive"))
      (node (ref "U$10") (pin "P2.5_GPIO") (pinfunction "P2.5_GPIO_P2.5_GPIO") (pintype "bidirectional"))
    )
    (net (code "28") (name "M_Z_RX") (class "Default")
      (node (ref "SERIAL_Z") (pin "2") (pinfunction "2_2") (pintype "passive"))
      (node (ref "U$13") (pin "P2.6_GPIO/PWM") (pinfunction "P2.6_GPIO/PWM_P2.6_GPIO/PWM") (pintype "bidirectional"))
    )
    (net (code "29") (name "M_Z_TX") (class "Default")
      (node (ref "SERIAL_Z") (pin "1") (pinfunction "1_1") (pintype "passive"))
      (node (ref "U$13") (pin "P2.5_GPIO") (pinfunction "P2.5_GPIO_P2.5_GPIO") (pintype "bidirectional"))
    )
    (net (code "30") (name "Net-(C1-Pad1)") (class "Default")
      (node (ref "C1") (pin "1") (pinfunction "1_1") (pintype "passive"))
      (node (ref "U$7") (pin "RETRY") (pinfunction "RETRY_RETRY") (pintype "bidirectional"))
    )
    (net (code "31") (name "Net-(C2-Pad1)") (class "Default")
      (node (ref "C2") (pin "1") (pinfunction "1_1") (pintype "passive"))
      (node (ref "U$7") (pin "CPN") (pinfunction "CPN_CPN") (pintype "bidirectional"))
    )
    (net (code "32") (name "Net-(C2-Pad2)") (class "Default")
      (node (ref "C2") (pin "2") (pinfunction "2_2") (pintype "passive"))
      (node (ref "U$7") (pin "CPP") (pinfunction "CPP_CPP") (pintype "bidirectional"))
    )
    (net (code "33") (name "Net-(C3-Pad2)") (class "Default")
      (node (ref "C3") (pin "2") (pinfunction "2_2") (pintype "passive"))
      (node (ref "U$7") (pin "VCP") (pinfunction "VCP_VCP") (pintype "bidirectional"))
    )
    (net (code "34") (name "Net-(C11-Pad1)") (class "Default")
      (node (ref "C11") (pin "1") (pinfunction "1_1") (pintype "passive"))
      (node (ref "U$12") (pin "RETRY") (pinfunction "RETRY_RETRY") (pintype "bidirectional"))
    )
    (net (code "35") (name "Net-(C12-Pad1)") (class "Default")
      (node (ref "C12") (pin "1") (pinfunction "1_1") (pintype "passive"))
      (node (ref "U$12") (pin "CPN") (pinfunction "CPN_CPN") (pintype "bidirectional"))
    )
    (net (code "36") (name "Net-(C12-Pad2)") (class "Default")
      (node (ref "C12") (pin "2") (pinfunction "2_2") (pintype "passive"))
      (node (ref "U$12") (pin "CPP") (pinfunction "CPP_CPP") (pintype "bidirectional"))
    )
    (net (code "37") (name "Net-(C13-Pad2)") (class "Default")
      (node (ref "C13") (pin "2") (pinfunction "2_2") (pintype "passive"))
      (node (ref "U$12") (pin "VCP") (pinfunction "VCP_VCP") (pintype "bidirectional"))
    )
    (net (code "38") (name "Net-(C18-Pad1)") (class "Default")
      (node (ref "C18") (pin "1") (pinfunction "1_1") (pintype "passive"))
      (node (ref "U$15") (pin "RETRY") (pinfunction "RETRY_RETRY") (pintype "bidirectional"))
    )
    (net (code "39") (name "Net-(C19-Pad1)") (class "Default")
      (node (ref "C19") (pin "1") (pinfunction "1_1") (pintype "passive"))
      (node (ref "U$15") (pin "CPN") (pinfunction "CPN_CPN") (pintype "bidirectional"))
    )
    (net (code "40") (name "Net-(C19-Pad2)") (class "Default")
      (node (ref "C19") (pin "2") (pinfunction "2_2") (pintype "passive"))
      (node (ref "U$15") (pin "CPP") (pinfunction "CPP_CPP") (pintype "bidirectional"))
    )
    (net (code "41") (name "Net-(C20-Pad2)") (class "Default")
      (node (ref "C20") (pin "2") (pinfunction "2_2") (pintype "passive"))
      (node (ref "U$15") (pin "VCP") (pinfunction "VCP_VCP") (pintype "bidirectional"))
    )
    (net (code "42") (name "Net-(CMTMOD_X-SIG)") (class "Default")
      (node (ref "CMTMOD_X") (pin "P$2") (pinfunction "SIG_P$2") (pintype "bidirectional"))
      (node (ref "U$7") (pin "CMTMOD") (pinfunction "CMTMOD_CMTMOD") (pintype "bidirectional"))
    )
    (net (code "43") (name "Net-(CMTMOD_Y-SIG)") (class "Default")
      (node (ref "CMTMOD_Y") (pin "P$2") (pinfunction "SIG_P$2") (pintype "bidirectional"))
      (node (ref "U$12") (pin "CMTMOD") (pinfunction "CMTMOD_CMTMOD") (pintype "bidirectional"))
    )
    (net (code "44") (name "Net-(CMTMOD_Z-SIG)") (class "Default")
      (node (ref "CMTMOD_Z") (pin "P$2") (pinfunction "SIG_P$2") (pintype "bidirectional"))
      (node (ref "U$15") (pin "CMTMOD") (pinfunction "CMTMOD_CMTMOD") (pintype "bidirectional"))
    )
    (net (code "45") (name "Net-(D1-PadC)") (class "Default")
      (node (ref "D1") (pin "C") (pinfunction "C_C") (pintype "passive"))
      (node (ref "R9") (pin "2") (pinfunction "2_2") (pintype "passive"))
    )
    (net (code "46") (name "Net-(D3-PadC)") (class "Default")
      (node (ref "D3") (pin "C") (pinfunction "C_C") (pintype "passive"))
      (node (ref "R10") (pin "2") (pinfunction "2_2") (pintype "passive"))
    )
    (net (code "47") (name "Net-(D4-PadC)") (class "Default")
      (node (ref "D4") (pin "C") (pinfunction "C_C") (pintype "passive"))
      (node (ref "R11") (pin "2") (pinfunction "2_2") (pintype "passive"))
    )
    (net (code "48") (name "Net-(D5-+)") (class "Default")
      (node (ref "C32") (pin "2") (pinfunction "2_2") (pintype "passive"))
      (node (ref "D5") (pin "P$1") (pinfunction "+_P$1") (pintype "bidirectional"))
      (node (ref "L2") (pin "P$1") (pinfunction "1A_P$1") (pintype "bidirectional"))
    )
    (net (code "49") (name "Net-(DAA_X-SIG)") (class "Default")
      (node (ref "DAA_X") (pin "P$2") (pinfunction "SIG_P$2") (pintype "bidirectional"))
      (node (ref "U$7") (pin "DAA") (pinfunction "DAA_DAA") (pintype "bidirectional"))
    )
    (net (code "50") (name "Net-(DAA_Y-SIG)") (class "Default")
      (node (ref "DAA_Y") (pin "P$2") (pinfunction "SIG_P$2") (pintype "bidirectional"))
      (node (ref "U$12") (pin "DAA") (pinfunction "DAA_DAA") (pintype "bidirectional"))
    )
    (net (code "51") (name "Net-(DAA_Z-SIG)") (class "Default")
      (node (ref "DAA_Z") (pin "P$2") (pinfunction "SIG_P$2") (pintype "bidirectional"))
      (node (ref "U$15") (pin "DAA") (pinfunction "DAA_DAA") (pintype "bidirectional"))
    )
    (net (code "52") (name "Net-(L2-2A)") (class "Default")
      (node (ref "C32") (pin "1") (pinfunction "1_1") (pintype "passive"))
      (node (ref "L2") (pin "P$3") (pinfunction "2A_P$3") (pintype "bidirectional"))
      (node (ref "U$6") (pin "P$3") (pinfunction "SW_P$3") (pintype "bidirectional"))
      (node (ref "U$6") (pin "P$4") (pinfunction "SW_P$4") (pintype "bidirectional"))
    )
    (net (code "53") (name "Net-(MOTOR_X-PadP$1)") (class "Default")
      (node (ref "MOTOR_X") (pin "P$1") (pinfunction "P$1_P$1") (pintype "bidirectional"))
      (node (ref "U$7") (pin "W") (pinfunction "W_W") (pintype "bidirectional"))
    )
    (net (code "54") (name "Net-(MOTOR_X-PadP$2)") (class "Default")
      (node (ref "MOTOR_X") (pin "P$2") (pinfunction "P$2_P$2") (pintype "bidirectional"))
      (node (ref "U$7") (pin "V") (pinfunction "V_V") (pintype "bidirectional"))
    )
    (net (code "55") (name "Net-(MOTOR_X-PadP$3)") (class "Default")
      (node (ref "MOTOR_X") (pin "P$3") (pinfunction "P$3_P$3") (pintype "bidirectional"))
      (node (ref "U$7") (pin "U") (pinfunction "U_U") (pintype "bidirectional"))
    )
    (net (code "56") (name "Net-(MOTOR_Y-PadP$1)") (class "Default")
      (node (ref "MOTOR_Y") (pin "P$1") (pinfunction "P$1_P$1") (pintype "bidirectional"))
      (node (ref "U$12") (pin "W") (pinfunction "W_W") (pintype "bidirectional"))
    )
    (net (code "57") (name "Net-(MOTOR_Y-PadP$2)") (class "Default")
      (node (ref "MOTOR_Y") (pin "P$2") (pinfunction "P$2_P$2") (pintype "bidirectional"))
      (node (ref "U$12") (pin "V") (pinfunction "V_V") (pintype "bidirectional"))
    )
    (net (code "58") (name "Net-(MOTOR_Y-PadP$3)") (class "Default")
      (node (ref "MOTOR_Y") (pin "P$3") (pinfunction "P$3_P$3") (pintype "bidirectional"))
      (node (ref "U$12") (pin "U") (pinfunction "U_U") (pintype "bidirectional"))
    )
    (net (code "59") (name "Net-(MOTOR_Z-PadP$1)") (class "Default")
      (node (ref "MOTOR_Z") (pin "P$1") (pinfunction "P$1_P$1") (pintype "bidirectional"))
      (node (ref "U$15") (pin "W") (pinfunction "W_W") (pintype "bidirectional"))
    )
    (net (code "60") (name "Net-(MOTOR_Z-PadP$2)") (class "Default")
      (node (ref "MOTOR_Z") (pin "P$2") (pinfunction "P$2_P$2") (pintype "bidirectional"))
      (node (ref "U$15") (pin "V") (pinfunction "V_V") (pintype "bidirectional"))
    )
    (net (code "61") (name "Net-(MOTOR_Z-PadP$3)") (class "Default")
      (node (ref "MOTOR_Z") (pin "P$3") (pinfunction "P$3_P$3") (pintype "bidirectional"))
      (node (ref "U$15") (pin "U") (pinfunction "U_U") (pintype "bidirectional"))
    )
    (net (code "62") (name "Net-(MSP_X_DEBUG-P2.0_TXD)") (class "Default")
      (node (ref "MSP_X_DEBUG") (pin "3") (pinfunction "P2.0_TXD_3") (pintype "bidirectional"))
      (node (ref "U$3") (pin "P2.0_TXD") (pinfunction "P2.0_TXD_P2.0_TXD") (pintype "bidirectional"))
    )
    (net (code "63") (name "Net-(MSP_X_DEBUG-P2.1_RXD)") (class "Default")
      (node (ref "MSP_X_DEBUG") (pin "4") (pinfunction "P2.1_RXD_4") (pintype "bidirectional"))
      (node (ref "U$3") (pin "P2.1_RXD") (pinfunction "P2.1_RXD_P2.1_RXD") (pintype "bidirectional"))
    )
    (net (code "64") (name "Net-(MSP_X_DEBUG-P3.4_GPIO_DEBUG)") (class "Default")
      (node (ref "MSP_X_DEBUG") (pin "7") (pinfunction "P3.4_GPIO_DEBUG_7") (pintype "bidirectional"))
      (node (ref "U$3") (pin "P3.4_GPIO_DEBUG") (pinfunction "P3.4_GPIO_DEBUG_P3.4_GPIO_DEBUG") (pintype "bidirectional"))
    )
    (net (code "65") (name "Net-(MSP_X_DEBUG-P3.5_GPIO_DEBUG)") (class "Default")
      (node (ref "D1") (pin "A") (pinfunction "A_A") (pintype "passive"))
      (node (ref "MSP_X_DEBUG") (pin "8") (pinfunction "P3.5_GPIO_DEBUG_8") (pintype "bidirectional"))
      (node (ref "U$3") (pin "P3.5_GPIO_DEBUG") (pinfunction "P3.5_GPIO_DEBUG_P3.5_GPIO_DEBUG") (pintype "bidirectional"))
    )
    (net (code "66") (name "Net-(MSP_X_DEBUG-PadSBWTCK)") (class "Default")
      (node (ref "MSP_X_DEBUG") (pin "SBWTCK") (pinfunction "SBWTCK_SBWTCK") (pintype "bidirectional"))
      (node (ref "U$3") (pin "SBWTCK") (pinfunction "SBWTCK_SBWTCK") (pintype "bidirectional"))
    )
    (net (code "67") (name "Net-(MSP_X_DEBUG-SBWTDIO)") (class "Default")
      (node (ref "MSP_X_DEBUG") (pin "2") (pinfunction "SBWTDIO_2") (pintype "bidirectional"))
      (node (ref "U$3") (pin "SBWTDIO") (pinfunction "SBWTDIO_SBWTDIO") (pintype "bidirectional"))
    )
    (net (code "68") (name "Net-(MSP_Y_DEBUG-P2.0_TXD)") (class "Default")
      (node (ref "MSP_Y_DEBUG") (pin "3") (pinfunction "P2.0_TXD_3") (pintype "bidirectional"))
      (node (ref "U$10") (pin "P2.0_TXD") (pinfunction "P2.0_TXD_P2.0_TXD") (pintype "bidirectional"))
    )
    (net (code "69") (name "Net-(MSP_Y_DEBUG-P2.1_RXD)") (class "Default")
      (node (ref "MSP_Y_DEBUG") (pin "4") (pinfunction "P2.1_RXD_4") (pintype "bidirectional"))
      (node (ref "U$10") (pin "P2.1_RXD") (pinfunction "P2.1_RXD_P2.1_RXD") (pintype "bidirectional"))
    )
    (net (code "70") (name "Net-(MSP_Y_DEBUG-P3.4_GPIO_DEBUG)") (class "Default")
      (node (ref "MSP_Y_DEBUG") (pin "7") (pinfunction "P3.4_GPIO_DEBUG_7") (pintype "bidirectional"))
      (node (ref "U$10") (pin "P3.4_GPIO_DEBUG") (pinfunction "P3.4_GPIO_DEBUG_P3.4_GPIO_DEBUG") (pintype "bidirectional"))
    )
    (net (code "71") (name "Net-(MSP_Y_DEBUG-P3.5_GPIO_DEBUG)") (class "Default")
      (node (ref "D3") (pin "A") (pinfunction "A_A") (pintype "passive"))
      (node (ref "MSP_Y_DEBUG") (pin "8") (pinfunction "P3.5_GPIO_DEBUG_8") (pintype "bidirectional"))
      (node (ref "U$10") (pin "P3.5_GPIO_DEBUG") (pinfunction "P3.5_GPIO_DEBUG_P3.5_GPIO_DEBUG") (pintype "bidirectional"))
    )
    (net (code "72") (name "Net-(MSP_Y_DEBUG-PadSBWTCK)") (class "Default")
      (node (ref "MSP_Y_DEBUG") (pin "SBWTCK") (pinfunction "SBWTCK_SBWTCK") (pintype "bidirectional"))
      (node (ref "U$10") (pin "SBWTCK") (pinfunction "SBWTCK_SBWTCK") (pintype "bidirectional"))
    )
    (net (code "73") (name "Net-(MSP_Y_DEBUG-SBWTDIO)") (class "Default")
      (node (ref "MSP_Y_DEBUG") (pin "2") (pinfunction "SBWTDIO_2") (pintype "bidirectional"))
      (node (ref "U$10") (pin "SBWTDIO") (pinfunction "SBWTDIO_SBWTDIO") (pintype "bidirectional"))
    )
    (net (code "74") (name "Net-(MSP_Z_DEBUG-P2.0_TXD)") (class "Default")
      (node (ref "MSP_Z_DEBUG") (pin "3") (pinfunction "P2.0_TXD_3") (pintype "bidirectional"))
      (node (ref "U$13") (pin "P2.0_TXD") (pinfunction "P2.0_TXD_P2.0_TXD") (pintype "bidirectional"))
    )
    (net (code "75") (name "Net-(MSP_Z_DEBUG-P2.1_RXD)") (class "Default")
      (node (ref "MSP_Z_DEBUG") (pin "4") (pinfunction "P2.1_RXD_4") (pintype "bidirectional"))
      (node (ref "U$13") (pin "P2.1_RXD") (pinfunction "P2.1_RXD_P2.1_RXD") (pintype "bidirectional"))
    )
    (net (code "76") (name "Net-(MSP_Z_DEBUG-P3.4_GPIO_DEBUG)") (class "Default")
      (node (ref "MSP_Z_DEBUG") (pin "7") (pinfunction "P3.4_GPIO_DEBUG_7") (pintype "bidirectional"))
      (node (ref "U$13") (pin "P3.4_GPIO_DEBUG") (pinfunction "P3.4_GPIO_DEBUG_P3.4_GPIO_DEBUG") (pintype "bidirectional"))
    )
    (net (code "77") (name "Net-(MSP_Z_DEBUG-P3.5_GPIO_DEBUG)") (class "Default")
      (node (ref "D4") (pin "A") (pinfunction "A_A") (pintype "passive"))
      (node (ref "MSP_Z_DEBUG") (pin "8") (pinfunction "P3.5_GPIO_DEBUG_8") (pintype "bidirectional"))
      (node (ref "U$13") (pin "P3.5_GPIO_DEBUG") (pinfunction "P3.5_GPIO_DEBUG_P3.5_GPIO_DEBUG") (pintype "bidirectional"))
    )
    (net (code "78") (name "Net-(MSP_Z_DEBUG-PadSBWTCK)") (class "Default")
      (node (ref "MSP_Z_DEBUG") (pin "SBWTCK") (pinfunction "SBWTCK_SBWTCK") (pintype "bidirectional"))
      (node (ref "U$13") (pin "SBWTCK") (pinfunction "SBWTCK_SBWTCK") (pintype "bidirectional"))
    )
    (net (code "79") (name "Net-(MSP_Z_DEBUG-SBWTDIO)") (class "Default")
      (node (ref "MSP_Z_DEBUG") (pin "2") (pinfunction "SBWTDIO_2") (pintype "bidirectional"))
      (node (ref "U$13") (pin "SBWTDIO") (pinfunction "SBWTDIO_SBWTDIO") (pintype "bidirectional"))
    )
    (net (code "80") (name "Net-(R2-Pad2)") (class "Default")
      (node (ref "R2") (pin "2") (pinfunction "2_2") (pintype "passive"))
      (node (ref "R3") (pin "1") (pinfunction "1_1") (pintype "passive"))
      (node (ref "U$7") (pin "U_HN") (pinfunction "U_HN_U_HN") (pintype "bidirectional"))
      (node (ref "U$7") (pin "V_HN") (pinfunction "V_HN_V_HN") (pintype "bidirectional"))
      (node (ref "U$7") (pin "W_HN") (pinfunction "W_HN_W_HN") (pintype "bidirectional"))
    )
    (net (code "81") (name "Net-(R7-Pad2)") (class "Default")
      (node (ref "R7") (pin "2") (pinfunction "2_2") (pintype "passive"))
      (node (ref "U$7") (pin "CS") (pinfunction "CS_CS") (pintype "bidirectional"))
    )
    (net (code "82") (name "Net-(R18-Pad2)") (class "Default")
      (node (ref "R18") (pin "2") (pinfunction "2_2") (pintype "passive"))
      (node (ref "R19") (pin "1") (pinfunction "1_1") (pintype "passive"))
      (node (ref "U$12") (pin "U_HN") (pinfunction "U_HN_U_HN") (pintype "bidirectional"))
      (node (ref "U$12") (pin "V_HN") (pinfunction "V_HN_V_HN") (pintype "bidirectional"))
      (node (ref "U$12") (pin "W_HN") (pinfunction "W_HN_W_HN") (pintype "bidirectional"))
    )
    (net (code "83") (name "Net-(R23-Pad2)") (class "Default")
      (node (ref "R23") (pin "2") (pinfunction "2_2") (pintype "passive"))
      (node (ref "U$12") (pin "CS") (pinfunction "CS_CS") (pintype "bidirectional"))
    )
    (net (code "84") (name "Net-(R26-Pad2)") (class "Default")
      (node (ref "R26") (pin "2") (pinfunction "2_2") (pintype "passive"))
      (node (ref "R27") (pin "1") (pinfunction "1_1") (pintype "passive"))
      (node (ref "U$15") (pin "U_HN") (pinfunction "U_HN_U_HN") (pintype "bidirectional"))
      (node (ref "U$15") (pin "V_HN") (pinfunction "V_HN_V_HN") (pintype "bidirectional"))
      (node (ref "U$15") (pin "W_HN") (pinfunction "W_HN_W_HN") (pintype "bidirectional"))
    )
    (net (code "85") (name "Net-(R31-Pad2)") (class "Default")
      (node (ref "R31") (pin "2") (pinfunction "2_2") (pintype "passive"))
      (node (ref "U$15") (pin "CS") (pinfunction "CS_CS") (pintype "bidirectional"))
    )
    (net (code "86") (name "Net-(U$6-EN{slash}UVLO)") (class "Default")
      (node (ref "R15") (pin "2") (pinfunction "2_2") (pintype "passive"))
      (node (ref "U$6") (pin "P$8") (pinfunction "EN/UVLO_P$8") (pintype "bidirectional"))
    )
    (net (code "87") (name "Net-(U$6-FBX)") (class "Default")
      (node (ref "C34") (pin "2") (pinfunction "2_2") (pintype "passive"))
      (node (ref "R16") (pin "1") (pinfunction "1_1") (pintype "passive"))
      (node (ref "R33") (pin "2") (pinfunction "2_2") (pintype "passive"))
      (node (ref "U$6") (pin "P$1") (pinfunction "FBX_P$1") (pintype "bidirectional"))
    )
    (net (code "88") (name "Net-(U$6-INT_VCC)") (class "Default")
      (node (ref "C27") (pin "1") (pinfunction "1_1") (pintype "passive"))
      (node (ref "U$6") (pin "P$7") (pinfunction "INT_VCC_P$7") (pintype "bidirectional"))
    )
    (net (code "89") (name "Net-(U2-BYP)") (class "Default")
      (node (ref "C16") (pin "2") (pinfunction "2_2") (pintype "passive"))
      (node (ref "U2") (pin "P$4") (pinfunction "BYP_P$4") (pintype "bidirectional"))
    )
    (net (code "90") (name "Net-(U3-BYP)") (class "Default")
      (node (ref "C29") (pin "2") (pinfunction "2_2") (pintype "passive"))
      (node (ref "U3") (pin "P$4") (pinfunction "BYP_P$4") (pintype "bidirectional"))
    )
    (net (code "91") (name "PWM_X") (class "Default")
      (node (ref "MOTOR_X_DEBUG") (pin "3") (pinfunction "3_3") (pintype "passive"))
      (node (ref "U$3") (pin "P1.7_GPIO/PWM") (pinfunction "P1.7_GPIO/PWM_P1.7_GPIO/PWM") (pintype "bidirectional"))
      (node (ref "U$7") (pin "PWM") (pinfunction "PWM_PWM") (pintype "bidirectional"))
    )
    (net (code "92") (name "PWM_Y") (class "Default")
      (node (ref "MOTOR_Y_DEBUG") (pin "3") (pinfunction "3_3") (pintype "passive"))
      (node (ref "U$10") (pin "P1.7_GPIO/PWM") (pinfunction "P1.7_GPIO/PWM_P1.7_GPIO/PWM") (pintype "bidirectional"))
      (node (ref "U$12") (pin "PWM") (pinfunction "PWM_PWM") (pintype "bidirectional"))
    )
    (net (code "93") (name "PWM_Z") (class "Default")
      (node (ref "MOTOR_Z_DEBUG") (pin "3") (pinfunction "3_3") (pintype "passive"))
      (node (ref "U$13") (pin "P1.7_GPIO/PWM") (pinfunction "P1.7_GPIO/PWM_P1.7_GPIO/PWM") (pintype "bidirectional"))
      (node (ref "U$15") (pin "PWM") (pinfunction "PWM_PWM") (pintype "bidirectional"))
    )
    (net (code "94") (name "RD_X") (class "Default")
      (node (ref "R1") (pin "1") (pinfunction "1_1") (pintype "passive"))
      (node (ref "U$3") (pin "P4.0_GPIO") (pinfunction "P4.0_GPIO_P4.0_GPIO") (pintype "bidirectional"))
      (node (ref "U$7") (pin "RD") (pinfunction "RD_RD") (pintype "bidirectional"))
    )
    (net (code "95") (name "RD_Y") (class "Default")
      (node (ref "R17") (pin "1") (pinfunction "1_1") (pintype "passive"))
      (node (ref "U$10") (pin "P4.0_GPIO") (pinfunction "P4.0_GPIO_P4.0_GPIO") (pintype "bidirectional"))
      (node (ref "U$12") (pin "RD") (pinfunction "RD_RD") (pintype "bidirectional"))
    )
    (net (code "96") (name "RD_Z") (class "Default")
      (node (ref "R25") (pin "1") (pinfunction "1_1") (pintype "passive"))
      (node (ref "U$13") (pin "P4.0_GPIO") (pinfunction "P4.0_GPIO_P4.0_GPIO") (pintype "bidirectional"))
      (node (ref "U$15") (pin "RD") (pinfunction "RD_RD") (pintype "bidirectional"))
    )
    (net (code "97") (name "SYNC1") (class "Default")
      (node (ref "PC104") (pin "P$45") (pinfunction "SYNC1_P$45") (pintype "bidirectional"))
      (node (ref "U$10") (pin "P7.2_SYNC1") (pinfunction "P7.2_SYNC1_P7.2_SYNC1") (pintype "bidirectional"))
      (node (ref "U$13") (pin "P7.2_SYNC1") (pinfunction "P7.2_SYNC1_P7.2_SYNC1") (pintype "bidirectional"))
      (node (ref "U$3") (pin "P7.2_SYNC1") (pinfunction "P7.2_SYNC1_P7.2_SYNC1") (pintype "bidirectional"))
    )
    (net (code "98") (name "SYNC2") (class "Default")
      (node (ref "PC104") (pin "P$49") (pinfunction "SYNC2_P$49") (pintype "bidirectional"))
      (node (ref "U$10") (pin "PJ.3_SYNC2") (pinfunction "PJ.3_SYNC2_PJ.3_SYNC2") (pintype "bidirectional"))
      (node (ref "U$13") (pin "PJ.3_SYNC2") (pinfunction "PJ.3_SYNC2_PJ.3_SYNC2") (pintype "bidirectional"))
      (node (ref "U$3") (pin "PJ.3_SYNC2") (pinfunction "PJ.3_SYNC2_PJ.3_SYNC2") (pintype "bidirectional"))
    )
    (net (code "99") (name "VBAT") (class "Default")
      (node (ref "C17") (pin "2") (pinfunction "2_2") (pintype "passive"))
      (node (ref "C26") (pin "1") (pinfunction "1_1") (pintype "passive"))
      (node (ref "C30") (pin "2") (pinfunction "2_2") (pintype "passive"))
      (node (ref "C8") (pin "1") (pinfunction "1_1") (pintype "passive"))
      (node (ref "L2") (pin "P$4") (pinfunction "2B_P$4") (pintype "bidirectional"))
      (node (ref "PC104") (pin "P$69") (pinfunction "WHEEL_VBATT_P$69") (pintype "bidirectional"))
      (node (ref "PC104") (pin "P$70") (pinfunction "WHEEL_VBATT_P$70") (pintype "bidirectional"))
      (node (ref "R15") (pin "1") (pinfunction "1_1") (pintype "passive"))
      (node (ref "U$6") (pin "P$6") (pinfunction "V_IN_P$6") (pintype "bidirectional"))
      (node (ref "U2") (pin "P$1") (pinfunction "IN_P$1") (pintype "bidirectional"))
      (node (ref "U2") (pin "P$3") (pinfunction "EN_P$3") (pintype "bidirectional"))
      (node (ref "U3") (pin "P$1") (pinfunction "IN_P$1") (pintype "bidirectional"))
      (node (ref "U3") (pin "P$3") (pinfunction "EN_P$3") (pintype "bidirectional"))
    )
    (net (code "100") (name "VINT_X") (class "Default")
      (node (ref "C4") (pin "2") (pinfunction "2_2") (pintype "passive"))
      (node (ref "CMTMOD_X") (pin "P$3") (pinfunction "VCC_P$3") (pintype "bidirectional"))
      (node (ref "DAA_X") (pin "P$3") (pinfunction "VCC_P$3") (pintype "bidirectional"))
      (node (ref "MOTOR_X") (pin "P$5") (pinfunction "P$5_P$5") (pintype "bidirectional"))
      (node (ref "R1") (pin "2") (pinfunction "2_2") (pintype "passive"))
      (node (ref "R3") (pin "2") (pinfunction "2_2") (pintype "passive"))
      (node (ref "R4") (pin "1") (pinfunction "1_1") (pintype "passive"))
      (node (ref "R5") (pin "1") (pinfunction "1_1") (pintype "passive"))
      (node (ref "R6") (pin "1") (pinfunction "1_1") (pintype "passive"))
      (node (ref "R8") (pin "1") (pinfunction "1_1") (pintype "passive"))
      (node (ref "U$7") (pin "VINT") (pinfunction "VINT_VINT") (pintype "bidirectional"))
    )
    (net (code "101") (name "VINT_Y") (class "Default")
      (node (ref "C14") (pin "2") (pinfunction "2_2") (pintype "passive"))
      (node (ref "CMTMOD_Y") (pin "P$3") (pinfunction "VCC_P$3") (pintype "bidirectional"))
      (node (ref "DAA_Y") (pin "P$3") (pinfunction "VCC_P$3") (pintype "bidirectional"))
      (node (ref "MOTOR_Y") (pin "P$5") (pinfunction "P$5_P$5") (pintype "bidirectional"))
      (node (ref "R17") (pin "2") (pinfunction "2_2") (pintype "passive"))
      (node (ref "R19") (pin "2") (pinfunction "2_2") (pintype "passive"))
      (node (ref "R20") (pin "1") (pinfunction "1_1") (pintype "passive"))
      (node (ref "R21") (pin "1") (pinfunction "1_1") (pintype "passive"))
      (node (ref "R22") (pin "1") (pinfunction "1_1") (pintype "passive"))
      (node (ref "R24") (pin "1") (pinfunction "1_1") (pintype "passive"))
      (node (ref "U$12") (pin "VINT") (pinfunction "VINT_VINT") (pintype "bidirectional"))
    )
    (net (code "102") (name "VINT_Z") (class "Default")
      (node (ref "C21") (pin "2") (pinfunction "2_2") (pintype "passive"))
      (node (ref "CMTMOD_Z") (pin "P$3") (pinfunction "VCC_P$3") (pintype "bidirectional"))
      (node (ref "DAA_Z") (pin "P$3") (pinfunction "VCC_P$3") (pintype "bidirectional"))
      (node (ref "MOTOR_Z") (pin "P$5") (pinfunction "P$5_P$5") (pintype "bidirectional"))
      (node (ref "R25") (pin "2") (pinfunction "2_2") (pintype "passive"))
      (node (ref "R27") (pin "2") (pinfunction "2_2") (pintype "passive"))
      (node (ref "R28") (pin "1") (pinfunction "1_1") (pintype "passive"))
      (node (ref "R29") (pin "1") (pinfunction "1_1") (pintype "passive"))
      (node (ref "R30") (pin "1") (pinfunction "1_1") (pintype "passive"))
      (node (ref "R32") (pin "1") (pinfunction "1_1") (pintype "passive"))
      (node (ref "U$15") (pin "VINT") (pinfunction "VINT_VINT") (pintype "bidirectional"))
    )
    (net (code "103") (name "VM") (class "Default")
      (node (ref "C15") (pin "2") (pinfunction "2_2") (pintype "passive"))
      (node (ref "C22") (pin "2") (pinfunction "2_2") (pintype "passive"))
      (node (ref "C33") (pin "1") (pinfunction "1_1") (pintype "passive"))
      (node (ref "C34") (pin "1") (pinfunction "1_1") (pintype "passive"))
      (node (ref "C35") (pin "1") (pinfunction "1_1") (pintype "passive"))
      (node (ref "C36") (pin "1") (pinfunction "1_1") (pintype "passive"))
      (node (ref "C5") (pin "2") (pinfunction "2_2") (pintype "passive"))
      (node (ref "D5") (pin "P$2") (pinfunction "-_P$2") (pintype "bidirectional"))
      (node (ref "R16") (pin "2") (pinfunction "2_2") (pintype "passive"))
      (node (ref "U$12") (pin "VM") (pinfunction "VM_VM") (pintype "bidirectional"))
      (node (ref "U$15") (pin "VM") (pinfunction "VM_VM") (pintype "bidirectional"))
      (node (ref "U$7") (pin "VM") (pinfunction "VM_VM") (pintype "bidirectional"))
    )
    (net (code "104") (name "unconnected-(PC104-BATT_VBAT$33-PadP$33)") (class "Default")
      (node (ref "PC104") (pin "P$33") (pinfunction "BATT_VBAT$33_P$33") (pintype "bidirectional"))
    )
    (net (code "105") (name "unconnected-(PC104-BATT_VBATT$34-PadP$34)") (class "Default")
      (node (ref "PC104") (pin "P$34") (pinfunction "BATT_VBATT$34_P$34") (pintype "bidirectional"))
    )
    (net (code "106") (name "unconnected-(PC104-BDOT_3.3V-PadP$83)") (class "Default")
      (node (ref "PC104") (pin "P$83") (pinfunction "BDOT_3.3V_P$83") (pintype "bidirectional"))
    )
    (net (code "107") (name "unconnected-(PC104-BDOT_3.3V-PadP$84)") (class "Default")
      (node (ref "PC104") (pin "P$84") (pinfunction "BDOT_3.3V_P$84") (pintype "bidirectional"))
    )
    (net (code "108") (name "unconnected-(PC104-BDOT_5V-PadP$81)") (class "Default")
      (node (ref "PC104") (pin "P$81") (pinfunction "BDOT_5V_P$81") (pintype "bidirectional"))
    )
    (net (code "109") (name "unconnected-(PC104-BDOT_5V-PadP$82)") (class "Default")
      (node (ref "PC104") (pin "P$82") (pinfunction "BDOT_5V_P$82") (pintype "bidirectional"))
    )
    (net (code "110") (name "unconnected-(PC104-BDOT_GND-PadP$87)") (class "Default")
      (node (ref "PC104") (pin "P$87") (pinfunction "BDOT_GND_P$87") (pintype "bidirectional"))
    )
    (net (code "111") (name "unconnected-(PC104-BDOT_GND-PadP$88)") (class "Default")
      (node (ref "PC104") (pin "P$88") (pinfunction "BDOT_GND_P$88") (pintype "bidirectional"))
    )
    (net (code "112") (name "unconnected-(PC104-BDOT_VBAT-PadP$85)") (class "Default")
      (node (ref "PC104") (pin "P$85") (pinfunction "BDOT_VBAT_P$85") (pintype "bidirectional"))
    )
    (net (code "113") (name "unconnected-(PC104-BDOT_VBAT-PadP$86)") (class "Default")
      (node (ref "PC104") (pin "P$86") (pinfunction "BDOT_VBAT_P$86") (pintype "bidirectional"))
    )
    (net (code "114") (name "unconnected-(PC104-COM1_GND-PadP$102)") (class "Default")
      (node (ref "PC104") (pin "P$102") (pinfunction "COM1_GND_P$102") (pintype "bidirectional"))
    )
    (net (code "115") (name "unconnected-(PC104-COM1_GND-PadP$104)") (class "Default")
      (node (ref "PC104") (pin "P$104") (pinfunction "COM1_GND_P$104") (pintype "bidirectional"))
    )
    (net (code "116") (name "unconnected-(PC104-COM1_VBAT-PadP$101)") (class "Default")
      (node (ref "PC104") (pin "P$101") (pinfunction "COM1_VBAT_P$101") (pintype "bidirectional"))
    )
    (net (code "117") (name "unconnected-(PC104-COM1_VBAT-PadP$103)") (class "Default")
      (node (ref "PC104") (pin "P$103") (pinfunction "COM1_VBAT_P$103") (pintype "bidirectional"))
    )
    (net (code "118") (name "unconnected-(PC104-COM2_GND-PadP$98)") (class "Default")
      (node (ref "PC104") (pin "P$98") (pinfunction "COM2_GND_P$98") (pintype "bidirectional"))
    )
    (net (code "119") (name "unconnected-(PC104-COM2_GND-PadP$100)") (class "Default")
      (node (ref "PC104") (pin "P$100") (pinfunction "COM2_GND_P$100") (pintype "bidirectional"))
    )
    (net (code "120") (name "unconnected-(PC104-COM2_VBAT-PadP$97)") (class "Default")
      (node (ref "PC104") (pin "P$97") (pinfunction "COM2_VBAT_P$97") (pintype "bidirectional"))
    )
    (net (code "121") (name "unconnected-(PC104-COM2_VBAT-PadP$99)") (class "Default")
      (node (ref "PC104") (pin "P$99") (pinfunction "COM2_VBAT_P$99") (pintype "bidirectional"))
    )
    (net (code "122") (name "unconnected-(PC104-DISTRI_GND-PadP$17)") (class "Default")
      (node (ref "PC104") (pin "P$17") (pinfunction "DISTRI_GND_P$17") (pintype "bidirectional"))
    )
    (net (code "123") (name "unconnected-(PC104-DISTRI_GND-PadP$19)") (class "Default")
      (node (ref "PC104") (pin "P$19") (pinfunction "DISTRI_GND_P$19") (pintype "bidirectional"))
    )
    (net (code "124") (name "unconnected-(PC104-DISTRI_GND-PadP$22)") (class "Default")
      (node (ref "PC104") (pin "P$22") (pinfunction "DISTRI_GND_P$22") (pintype "bidirectional"))
    )
    (net (code "125") (name "unconnected-(PC104-DISTRI_GND-PadP$24)") (class "Default")
      (node (ref "PC104") (pin "P$24") (pinfunction "DISTRI_GND_P$24") (pintype "bidirectional"))
    )
    (net (code "126") (name "unconnected-(PC104-DISTRI_GND-PadP$25)") (class "Default")
      (node (ref "PC104") (pin "P$25") (pinfunction "DISTRI_GND_P$25") (pintype "bidirectional"))
    )
    (net (code "127") (name "unconnected-(PC104-DISTRI_GND-PadP$27)") (class "Default")
      (node (ref "PC104") (pin "P$27") (pinfunction "DISTRI_GND_P$27") (pintype "bidirectional"))
    )
    (net (code "128") (name "unconnected-(PC104-DISTRI_GND-PadP$30)") (class "Default")
      (node (ref "PC104") (pin "P$30") (pinfunction "DISTRI_GND_P$30") (pintype "bidirectional"))
    )
    (net (code "129") (name "unconnected-(PC104-DISTRI_GND-PadP$32)") (class "Default")
      (node (ref "PC104") (pin "P$32") (pinfunction "DISTRI_GND_P$32") (pintype "bidirectional"))
    )
    (net (code "130") (name "unconnected-(PC104-DISTRI_VBAT-PadP$18)") (class "Default")
      (node (ref "PC104") (pin "P$18") (pinfunction "DISTRI_VBAT_P$18") (pintype "bidirectional"))
    )
    (net (code "131") (name "unconnected-(PC104-DISTRI_VBAT-PadP$20)") (class "Default")
      (node (ref "PC104") (pin "P$20") (pinfunction "DISTRI_VBAT_P$20") (pintype "bidirectional"))
    )
    (net (code "132") (name "unconnected-(PC104-DISTRI_VBAT-PadP$21)") (class "Default")
      (node (ref "PC104") (pin "P$21") (pinfunction "DISTRI_VBAT_P$21") (pintype "bidirectional"))
    )
    (net (code "133") (name "unconnected-(PC104-DISTRI_VBAT-PadP$23)") (class "Default")
      (node (ref "PC104") (pin "P$23") (pinfunction "DISTRI_VBAT_P$23") (pintype "bidirectional"))
    )
    (net (code "134") (name "unconnected-(PC104-DISTRI_VBAT-PadP$26)") (class "Default")
      (node (ref "PC104") (pin "P$26") (pinfunction "DISTRI_VBAT_P$26") (pintype "bidirectional"))
    )
    (net (code "135") (name "unconnected-(PC104-DISTRI_VBAT-PadP$28)") (class "Default")
      (node (ref "PC104") (pin "P$28") (pinfunction "DISTRI_VBAT_P$28") (pintype "bidirectional"))
    )
    (net (code "136") (name "unconnected-(PC104-DISTRI_VBAT-PadP$29)") (class "Default")
      (node (ref "PC104") (pin "P$29") (pinfunction "DISTRI_VBAT_P$29") (pintype "bidirectional"))
    )
    (net (code "137") (name "unconnected-(PC104-DISTRI_VBAT-PadP$31)") (class "Default")
      (node (ref "PC104") (pin "P$31") (pinfunction "DISTRI_VBAT_P$31") (pintype "bidirectional"))
    )
    (net (code "138") (name "unconnected-(PC104-ESTIMAT_3.3V-PadP$75)") (class "Default")
      (node (ref "PC104") (pin "P$75") (pinfunction "ESTIMAT_3.3V_P$75") (pintype "bidirectional"))
    )
    (net (code "139") (name "unconnected-(PC104-ESTIMAT_3.3V-PadP$76)") (class "Default")
      (node (ref "PC104") (pin "P$76") (pinfunction "ESTIMAT_3.3V_P$76") (pintype "bidirectional"))
    )
    (net (code "140") (name "unconnected-(PC104-ESTIMAT_5V-PadP$73)") (class "Default")
      (node (ref "PC104") (pin "P$73") (pinfunction "ESTIMAT_5V_P$73") (pintype "bidirectional"))
    )
    (net (code "141") (name "unconnected-(PC104-ESTIMAT_5V-PadP$74)") (class "Default")
      (node (ref "PC104") (pin "P$74") (pinfunction "ESTIMAT_5V_P$74") (pintype "bidirectional"))
    )
    (net (code "142") (name "unconnected-(PC104-ESTIMAT_GND-PadP$79)") (class "Default")
      (node (ref "PC104") (pin "P$79") (pinfunction "ESTIMAT_GND_P$79") (pintype "bidirectional"))
    )
    (net (code "143") (name "unconnected-(PC104-ESTIMAT_GND-PadP$80)") (class "Default")
      (node (ref "PC104") (pin "P$80") (pinfunction "ESTIMAT_GND_P$80") (pintype "bidirectional"))
    )
    (net (code "144") (name "unconnected-(PC104-ESTIMAT_VBAT-PadP$77)") (class "Default")
      (node (ref "PC104") (pin "P$77") (pinfunction "ESTIMAT_VBAT_P$77") (pintype "bidirectional"))
    )
    (net (code "145") (name "unconnected-(PC104-ESTIMAT_VBAT-PadP$78)") (class "Default")
      (node (ref "PC104") (pin "P$78") (pinfunction "ESTIMAT_VBAT_P$78") (pintype "bidirectional"))
    )
    (net (code "146") (name "unconnected-(PC104-GEN_VBATT$35-PadP$35)") (class "Default")
      (node (ref "PC104") (pin "P$35") (pinfunction "GEN_VBATT$35_P$35") (pintype "bidirectional"))
    )
    (net (code "147") (name "unconnected-(PC104-GEN_VBATT$36-PadP$36)") (class "Default")
      (node (ref "PC104") (pin "P$36") (pinfunction "GEN_VBATT$36_P$36") (pintype "bidirectional"))
    )
    (net (code "148") (name "unconnected-(PC104-P-PadP$59)") (class "Default")
      (node (ref "PC104") (pin "P$59") (pinfunction "P_P$59") (pintype "bidirectional"))
    )
    (net (code "149") (name "unconnected-(PC104-PPT_GND-PadP$1)") (class "Default")
      (node (ref "PC104") (pin "P$1") (pinfunction "PPT_GND_P$1") (pintype "bidirectional"))
    )
    (net (code "150") (name "unconnected-(PC104-PPT_GND-PadP$3)") (class "Default")
      (node (ref "PC104") (pin "P$3") (pinfunction "PPT_GND_P$3") (pintype "bidirectional"))
    )
    (net (code "151") (name "unconnected-(PC104-PPT_GND-PadP$6)") (class "Default")
      (node (ref "PC104") (pin "P$6") (pinfunction "PPT_GND_P$6") (pintype "bidirectional"))
    )
    (net (code "152") (name "unconnected-(PC104-PPT_GND-PadP$8)") (class "Default")
      (node (ref "PC104") (pin "P$8") (pinfunction "PPT_GND_P$8") (pintype "bidirectional"))
    )
    (net (code "153") (name "unconnected-(PC104-PPT_GND-PadP$9)") (class "Default")
      (node (ref "PC104") (pin "P$9") (pinfunction "PPT_GND_P$9") (pintype "bidirectional"))
    )
    (net (code "154") (name "unconnected-(PC104-PPT_GND-PadP$11)") (class "Default")
      (node (ref "PC104") (pin "P$11") (pinfunction "PPT_GND_P$11") (pintype "bidirectional"))
    )
    (net (code "155") (name "unconnected-(PC104-PPT_GND-PadP$14)") (class "Default")
      (node (ref "PC104") (pin "P$14") (pinfunction "PPT_GND_P$14") (pintype "bidirectional"))
    )
    (net (code "156") (name "unconnected-(PC104-PPT_GND-PadP$16)") (class "Default")
      (node (ref "PC104") (pin "P$16") (pinfunction "PPT_GND_P$16") (pintype "bidirectional"))
    )
    (net (code "157") (name "unconnected-(PC104-PPT_VBAT-PadP$2)") (class "Default")
      (node (ref "PC104") (pin "P$2") (pinfunction "PPT_VBAT_P$2") (pintype "bidirectional"))
    )
    (net (code "158") (name "unconnected-(PC104-PPT_VBAT-PadP$4)") (class "Default")
      (node (ref "PC104") (pin "P$4") (pinfunction "PPT_VBAT_P$4") (pintype "bidirectional"))
    )
    (net (code "159") (name "unconnected-(PC104-PPT_VBAT-PadP$5)") (class "Default")
      (node (ref "PC104") (pin "P$5") (pinfunction "PPT_VBAT_P$5") (pintype "bidirectional"))
    )
    (net (code "160") (name "unconnected-(PC104-PPT_VBAT-PadP$7)") (class "Default")
      (node (ref "PC104") (pin "P$7") (pinfunction "PPT_VBAT_P$7") (pintype "bidirectional"))
    )
    (net (code "161") (name "unconnected-(PC104-PPT_VBAT-PadP$10)") (class "Default")
      (node (ref "PC104") (pin "P$10") (pinfunction "PPT_VBAT_P$10") (pintype "bidirectional"))
    )
    (net (code "162") (name "unconnected-(PC104-PPT_VBAT-PadP$12)") (class "Default")
      (node (ref "PC104") (pin "P$12") (pinfunction "PPT_VBAT_P$12") (pintype "bidirectional"))
    )
    (net (code "163") (name "unconnected-(PC104-PPT_VBAT-PadP$13)") (class "Default")
      (node (ref "PC104") (pin "P$13") (pinfunction "PPT_VBAT_P$13") (pintype "bidirectional"))
    )
    (net (code "164") (name "unconnected-(PC104-PPT_VBAT-PadP$15)") (class "Default")
      (node (ref "PC104") (pin "P$15") (pinfunction "PPT_VBAT_P$15") (pintype "bidirectional"))
    )
    (net (code "165") (name "unconnected-(PC104-PadP$37)") (class "Default")
      (node (ref "PC104") (pin "P$37") (pinfunction "P$37_P$37") (pintype "bidirectional"))
    )
    (net (code "166") (name "unconnected-(PC104-PadP$38)") (class "Default")
      (node (ref "PC104") (pin "P$38") (pinfunction "P$38_P$38") (pintype "bidirectional"))
    )
    (net (code "167") (name "unconnected-(PC104-PadP$39)") (class "Default")
      (node (ref "PC104") (pin "P$39") (pinfunction "P$39_P$39") (pintype "bidirectional"))
    )
    (net (code "168") (name "unconnected-(PC104-PadP$40)") (class "Default")
      (node (ref "PC104") (pin "P$40") (pinfunction "P$40_P$40") (pintype "bidirectional"))
    )
    (net (code "169") (name "unconnected-(PC104-PadP$41)") (class "Default")
      (node (ref "PC104") (pin "P$41") (pinfunction "P$41_P$41") (pintype "bidirectional"))
    )
    (net (code "170") (name "unconnected-(PC104-PadP$42)") (class "Default")
      (node (ref "PC104") (pin "P$42") (pinfunction "P$42_P$42") (pintype "bidirectional"))
    )
    (net (code "171") (name "unconnected-(PC104-PadP$43)") (class "Default")
      (node (ref "PC104") (pin "P$43") (pinfunction "P$43_P$43") (pintype "bidirectional"))
    )
    (net (code "172") (name "unconnected-(PC104-PadP$44)") (class "Default")
      (node (ref "PC104") (pin "P$44") (pinfunction "P$44_P$44") (pintype "bidirectional"))
    )
    (net (code "173") (name "unconnected-(PC104-PadP$46)") (class "Default")
      (node (ref "PC104") (pin "P$46") (pinfunction "P$46_P$46") (pintype "bidirectional"))
    )
    (net (code "174") (name "unconnected-(PC104-PadP$47)") (class "Default")
      (node (ref "PC104") (pin "P$47") (pinfunction "P$47_P$47") (pintype "bidirectional"))
    )
    (net (code "175") (name "unconnected-(PC104-PadP$48)") (class "Default")
      (node (ref "PC104") (pin "P$48") (pinfunction "P$48_P$48") (pintype "bidirectional"))
    )
    (net (code "176") (name "unconnected-(PC104-PadP$50)") (class "Default")
      (node (ref "PC104") (pin "P$50") (pinfunction "P$50_P$50") (pintype "bidirectional"))
    )
    (net (code "177") (name "unconnected-(PC104-PadP$54)") (class "Default")
      (node (ref "PC104") (pin "P$54") (pinfunction "P$54_P$54") (pintype "bidirectional"))
    )
    (net (code "178") (name "unconnected-(PC104-PadP$58)") (class "Default")
      (node (ref "PC104") (pin "P$58") (pinfunction "P$58_P$58") (pintype "bidirectional"))
    )
    (net (code "179") (name "unconnected-(PC104-PadP$60)") (class "Default")
      (node (ref "PC104") (pin "P$60") (pinfunction "P$60_P$60") (pintype "bidirectional"))
    )
    (net (code "180") (name "unconnected-(PC104-PadP$61)") (class "Default")
      (node (ref "PC104") (pin "P$61") (pinfunction "P$61_P$61") (pintype "bidirectional"))
    )
    (net (code "181") (name "unconnected-(PC104-PadP$62)") (class "Default")
      (node (ref "PC104") (pin "P$62") (pinfunction "P$62_P$62") (pintype "bidirectional"))
    )
    (net (code "182") (name "unconnected-(PC104-PadP$63)") (class "Default")
      (node (ref "PC104") (pin "P$63") (pinfunction "P$63_P$63") (pintype "bidirectional"))
    )
    (net (code "183") (name "unconnected-(PC104-PadP$64)") (class "Default")
      (node (ref "PC104") (pin "P$64") (pinfunction "P$64_P$64") (pintype "bidirectional"))
    )
    (net (code "184") (name "unconnected-(PC104-PadP$65)") (class "Default")
      (node (ref "PC104") (pin "P$65") (pinfunction "P$65_P$65") (pintype "bidirectional"))
    )
    (net (code "185") (name "unconnected-(PC104-PadP$66)") (class "Default")
      (node (ref "PC104") (pin "P$66") (pinfunction "P$66_P$66") (pintype "bidirectional"))
    )
    (net (code "186") (name "unconnected-(PC104-PadP$67)") (class "Default")
      (node (ref "PC104") (pin "P$67") (pinfunction "P$67_P$67") (pintype "bidirectional"))
    )
    (net (code "187") (name "unconnected-(PC104-PadP$68)") (class "Default")
      (node (ref "PC104") (pin "P$68") (pinfunction "P$68_P$68") (pintype "bidirectional"))
    )
    (net (code "188") (name "unconnected-(PC104-PadP$89)") (class "Default")
      (node (ref "PC104") (pin "P$89") (pinfunction "P$89_P$89") (pintype "bidirectional"))
    )
    (net (code "189") (name "unconnected-(PC104-PadP$90)") (class "Default")
      (node (ref "PC104") (pin "P$90") (pinfunction "P$90_P$90") (pintype "bidirectional"))
    )
    (net (code "190") (name "unconnected-(PC104-PadP$91)") (class "Default")
      (node (ref "PC104") (pin "P$91") (pinfunction "P$91_P$91") (pintype "bidirectional"))
    )
    (net (code "191") (name "unconnected-(PC104-PadP$92)") (class "Default")
      (node (ref "PC104") (pin "P$92") (pinfunction "P$92_P$92") (pintype "bidirectional"))
    )
    (net (code "192") (name "unconnected-(PC104-PadP$95)") (class "Default")
      (node (ref "PC104") (pin "P$95") (pinfunction "P$95_P$95") (pintype "bidirectional"))
    )
    (net (code "193") (name "unconnected-(PC104-PadP$96)") (class "Default")
      (node (ref "PC104") (pin "P$96") (pinfunction "P$96_P$96") (pintype "bidirectional"))
    )
    (net (code "194") (name "unconnected-(PC104-RAHS_GND-PadP$94)") (class "Default")
      (node (ref "PC104") (pin "P$94") (pinfunction "RAHS_GND_P$94") (pintype "bidirectional"))
    )
    (net (code "195") (name "unconnected-(PC104-RAHS_VBAT-PadP$93)") (class "Default")
      (node (ref "PC104") (pin "P$93") (pinfunction "RAHS_VBAT_P$93") (pintype "bidirectional"))
    )
    (net (code "196") (name "unconnected-(PC104-TOPDEPLOY+-PadP$51)") (class "Default")
      (node (ref "PC104") (pin "P$51") (pinfunction "TOPDEPLOY+_P$51") (pintype "bidirectional"))
    )
    (net (code "197") (name "unconnected-(PC104-TOPDEPLOY+-PadP$55)") (class "Default")
      (node (ref "PC104") (pin "P$55") (pinfunction "TOPDEPLOY+_P$55") (pintype "bidirectional"))
    )
    (net (code "198") (name "unconnected-(PC104-TOPDEPLOY-$52-PadP$52)") (class "Default")
      (node (ref "PC104") (pin "P$52") (pinfunction "TOPDEPLOY-$52_P$52") (pintype "bidirectional"))
    )
    (net (code "199") (name "unconnected-(PC104-TOPDEPLOY-$56-PadP$56)") (class "Default")
      (node (ref "PC104") (pin "P$56") (pinfunction "TOPDEPLOY-$56_P$56") (pintype "bidirectional"))
    )
    (net (code "200") (name "unconnected-(U$3-P2.3_SPI-CS2-PadP2.4_SPI-CS2)") (class "Default")
      (node (ref "U$3") (pin "P2.4_SPI-CS2") (pinfunction "P2.3_SPI-CS2_P2.4_SPI-CS2") (pintype "bidirectional"))
    )
    (net (code "201") (name "unconnected-(U$3-PadP1.0_A0)") (class "Default")
      (node (ref "U$3") (pin "P1.0_A0") (pinfunction "P1.0_A0_P1.0_A0") (pintype "bidirectional"))
    )
    (net (code "202") (name "unconnected-(U$3-PadP1.1_A1)") (class "Default")
      (node (ref "U$3") (pin "P1.1_A1") (pinfunction "P1.1_A1_P1.1_A1") (pintype "bidirectional"))
    )
    (net (code "203") (name "unconnected-(U$3-PadP1.2_A2)") (class "Default")
      (node (ref "U$3") (pin "P1.2_A2") (pinfunction "P1.2_A2_P1.2_A2") (pintype "bidirectional"))
    )
    (net (code "204") (name "unconnected-(U$3-PadP1.3_A3)") (class "Default")
      (node (ref "U$3") (pin "P1.3_A3") (pinfunction "P1.3_A3_P1.3_A3") (pintype "bidirectional"))
    )
    (net (code "205") (name "unconnected-(U$3-PadP1.4_A4)") (class "Default")
      (node (ref "U$3") (pin "P1.4_A4") (pinfunction "P1.4_A4_P1.4_A4") (pintype "bidirectional"))
    )
    (net (code "206") (name "unconnected-(U$3-PadP1.5_A5)") (class "Default")
      (node (ref "U$3") (pin "P1.5_A5") (pinfunction "P1.5_A5_P1.5_A5") (pintype "bidirectional"))
    )
    (net (code "207") (name "unconnected-(U$3-PadP2.2_GPIO{slash}PWM)") (class "Default")
      (node (ref "U$3") (pin "P2.2_GPIO/PWM") (pinfunction "P2.2_GPIO/PWM_P2.2_GPIO/PWM") (pintype "bidirectional"))
    )
    (net (code "208") (name "unconnected-(U$3-PadP2.7_SPI-CS3)") (class "Default")
      (node (ref "U$3") (pin "P2.7_SPI-CS3") (pinfunction "P2.7_SPI-CS3_P2.7_SPI-CS3") (pintype "bidirectional"))
    )
    (net (code "209") (name "unconnected-(U$3-PadP3.0_A12)") (class "Default")
      (node (ref "U$3") (pin "P3.0_A12") (pinfunction "P3.0_A12_P3.0_A12") (pintype "bidirectional"))
    )
    (net (code "210") (name "unconnected-(U$3-PadP3.1_A13)") (class "Default")
      (node (ref "U$3") (pin "P3.1_A13") (pinfunction "P3.1_A13_P3.1_A13") (pintype "bidirectional"))
    )
    (net (code "211") (name "unconnected-(U$3-PadP3.2_A14)") (class "Default")
      (node (ref "U$3") (pin "P3.2_A14") (pinfunction "P3.2_A14_P3.2_A14") (pintype "bidirectional"))
    )
    (net (code "212") (name "unconnected-(U$3-PadP3.3_A15)") (class "Default")
      (node (ref "U$3") (pin "P3.3_A15") (pinfunction "P3.3_A15_P3.3_A15") (pintype "bidirectional"))
    )
    (net (code "213") (name "unconnected-(U$3-PadP4.1_GPIO)") (class "Default")
      (node (ref "U$3") (pin "P4.1_GPIO") (pinfunction "P4.1_GPIO_P4.1_GPIO") (pintype "bidirectional"))
    )
    (net (code "214") (name "unconnected-(U$3-PadP4.2_GPIO)") (class "Default")
      (node (ref "U$3") (pin "P4.2_GPIO") (pinfunction "P4.2_GPIO_P4.2_GPIO") (pintype "bidirectional"))
    )
    (net (code "215") (name "unconnected-(U$3-PadP5.0_I2C-SDA-1)") (class "Default")
      (node (ref "U$3") (pin "P5.0_I2C-SDA-1") (pinfunction "P5.0_I2C-SDA-1_P5.0_I2C-SDA-1") (pintype "bidirectional"))
    )
    (net (code "216") (name "unconnected-(U$3-PadP5.1_I2C-SCL-1)") (class "Default")
      (node (ref "U$3") (pin "P5.1_I2C-SCL-1") (pinfunction "P5.1_I2C-SCL-1_P5.1_I2C-SCL-1") (pintype "bidirectional"))
    )
    (net (code "217") (name "unconnected-(U$3-PadP5.4_SPI-MOSI)") (class "Default")
      (node (ref "U$3") (pin "P5.4_SPI-MOSI") (pinfunction "P5.4_SPI-MOSI_P5.4_SPI-MOSI") (pintype "bidirectional"))
    )
    (net (code "218") (name "unconnected-(U$3-PadP5.5_SPI-MISO)") (class "Default")
      (node (ref "U$3") (pin "P5.5_SPI-MISO") (pinfunction "P5.5_SPI-MISO_P5.5_SPI-MISO") (pintype "bidirectional"))
    )
    (net (code "219") (name "unconnected-(U$3-PadP5.6_SPI-CLK)") (class "Default")
      (node (ref "U$3") (pin "P5.6_SPI-CLK") (pinfunction "P5.6_SPI-CLK_P5.6_SPI-CLK") (pintype "bidirectional"))
    )
    (net (code "220") (name "unconnected-(U$3-PadP7.0_I2C-SDA-2)") (class "Default")
      (node (ref "U$3") (pin "P7.0_I2C-SDA-2") (pinfunction "P7.0_I2C-SDA-2_P7.0_I2C-SDA-2") (pintype "bidirectional"))
    )
    (net (code "221") (name "unconnected-(U$3-PadP7.1_I2C-SCL-2)") (class "Default")
      (node (ref "U$3") (pin "P7.1_I2C-SCL-2") (pinfunction "P7.1_I2C-SCL-2_P7.1_I2C-SCL-2") (pintype "bidirectional"))
    )
    (net (code "222") (name "unconnected-(U$6-NC-PadP$2)") (class "Default")
      (node (ref "U$6") (pin "P$2") (pinfunction "NC_P$2") (pintype "bidirectional"))
    )
    (net (code "223") (name "unconnected-(U$10-P2.3_SPI-CS2-PadP2.4_SPI-CS2)") (class "Default")
      (node (ref "U$10") (pin "P2.4_SPI-CS2") (pinfunction "P2.3_SPI-CS2_P2.4_SPI-CS2") (pintype "bidirectional"))
    )
    (net (code "224") (name "unconnected-(U$10-PadP1.0_A0)") (class "Default")
      (node (ref "U$10") (pin "P1.0_A0") (pinfunction "P1.0_A0_P1.0_A0") (pintype "bidirectional"))
    )
    (net (code "225") (name "unconnected-(U$10-PadP1.1_A1)") (class "Default")
      (node (ref "U$10") (pin "P1.1_A1") (pinfunction "P1.1_A1_P1.1_A1") (pintype "bidirectional"))
    )
    (net (code "226") (name "unconnected-(U$10-PadP1.2_A2)") (class "Default")
      (node (ref "U$10") (pin "P1.2_A2") (pinfunction "P1.2_A2_P1.2_A2") (pintype "bidirectional"))
    )
    (net (code "227") (name "unconnected-(U$10-PadP1.3_A3)") (class "Default")
      (node (ref "U$10") (pin "P1.3_A3") (pinfunction "P1.3_A3_P1.3_A3") (pintype "bidirectional"))
    )
    (net (code "228") (name "unconnected-(U$10-PadP1.4_A4)") (class "Default")
      (node (ref "U$10") (pin "P1.4_A4") (pinfunction "P1.4_A4_P1.4_A4") (pintype "bidirectional"))
    )
    (net (code "229") (name "unconnected-(U$10-PadP1.5_A5)") (class "Default")
      (node (ref "U$10") (pin "P1.5_A5") (pinfunction "P1.5_A5_P1.5_A5") (pintype "bidirectional"))
    )
    (net (code "230") (name "unconnected-(U$10-PadP2.2_GPIO{slash}PWM)") (class "Default")
      (node (ref "U$10") (pin "P2.2_GPIO/PWM") (pinfunction "P2.2_GPIO/PWM_P2.2_GPIO/PWM") (pintype "bidirectional"))
    )
    (net (code "231") (name "unconnected-(U$10-PadP2.7_SPI-CS3)") (class "Default")
      (node (ref "U$10") (pin "P2.7_SPI-CS3") (pinfunction "P2.7_SPI-CS3_P2.7_SPI-CS3") (pintype "bidirectional"))
    )
    (net (code "232") (name "unconnected-(U$10-PadP3.0_A12)") (class "Default")
      (node (ref "U$10") (pin "P3.0_A12") (pinfunction "P3.0_A12_P3.0_A12") (pintype "bidirectional"))
    )
    (net (code "233") (name "unconnected-(U$10-PadP3.1_A13)") (class "Default")
      (node (ref "U$10") (pin "P3.1_A13") (pinfunction "P3.1_A13_P3.1_A13") (pintype "bidirectional"))
    )
    (net (code "234") (name "unconnected-(U$10-PadP3.2_A14)") (class "Default")
      (node (ref "U$10") (pin "P3.2_A14") (pinfunction "P3.2_A14_P3.2_A14") (pintype "bidirectional"))
    )
    (net (code "235") (name "unconnected-(U$10-PadP3.3_A15)") (class "Default")
      (node (ref "U$10") (pin "P3.3_A15") (pinfunction "P3.3_A15_P3.3_A15") (pintype "bidirectional"))
    )
    (net (code "236") (name "unconnected-(U$10-PadP4.1_GPIO)") (class "Default")
      (node (ref "U$10") (pin "P4.1_GPIO") (pinfunction "P4.1_GPIO_P4.1_GPIO") (pintype "bidirectional"))
    )
    (net (code "237") (name "unconnected-(U$10-PadP4.2_GPIO)") (class "Default")
      (node (ref "U$10") (pin "P4.2_GPIO") (pinfunction "P4.2_GPIO_P4.2_GPIO") (pintype "bidirectional"))
    )
    (net (code "238") (name "unconnected-(U$10-PadP5.0_I2C-SDA-1)") (class "Default")
      (node (ref "U$10") (pin "P5.0_I2C-SDA-1") (pinfunction "P5.0_I2C-SDA-1_P5.0_I2C-SDA-1") (pintype "bidirectional"))
    )
    (net (code "239") (name "unconnected-(U$10-PadP5.1_I2C-SCL-1)") (class "Default")
      (node (ref "U$10") (pin "P5.1_I2C-SCL-1") (pinfunction "P5.1_I2C-SCL-1_P5.1_I2C-SCL-1") (pintype "bidirectional"))
    )
    (net (code "240") (name "unconnected-(U$10-PadP5.4_SPI-MOSI)") (class "Default")
      (node (ref "U$10") (pin "P5.4_SPI-MOSI") (pinfunction "P5.4_SPI-MOSI_P5.4_SPI-MOSI") (pintype "bidirectional"))
    )
    (net (code "241") (name "unconnected-(U$10-PadP5.5_SPI-MISO)") (class "Default")
      (node (ref "U$10") (pin "P5.5_SPI-MISO") (pinfunction "P5.5_SPI-MISO_P5.5_SPI-MISO") (pintype "bidirectional"))
    )
    (net (code "242") (name "unconnected-(U$10-PadP5.6_SPI-CLK)") (class "Default")
      (node (ref "U$10") (pin "P5.6_SPI-CLK") (pinfunction "P5.6_SPI-CLK_P5.6_SPI-CLK") (pintype "bidirectional"))
    )
    (net (code "243") (name "unconnected-(U$10-PadP7.0_I2C-SDA-2)") (class "Default")
      (node (ref "U$10") (pin "P7.0_I2C-SDA-2") (pinfunction "P7.0_I2C-SDA-2_P7.0_I2C-SDA-2") (pintype "bidirectional"))
    )
    (net (code "244") (name "unconnected-(U$10-PadP7.1_I2C-SCL-2)") (class "Default")
      (node (ref "U$10") (pin "P7.1_I2C-SCL-2") (pinfunction "P7.1_I2C-SCL-2_P7.1_I2C-SCL-2") (pintype "bidirectional"))
    )
    (net (code "245") (name "unconnected-(U$13-P2.3_SPI-CS2-PadP2.4_SPI-CS2)") (class "Default")
      (node (ref "U$13") (pin "P2.4_SPI-CS2") (pinfunction "P2.3_SPI-CS2_P2.4_SPI-CS2") (pintype "bidirectional"))
    )
    (net (code "246") (name "unconnected-(U$13-PadP1.0_A0)") (class "Default")
      (node (ref "U$13") (pin "P1.0_A0") (pinfunction "P1.0_A0_P1.0_A0") (pintype "bidirectional"))
    )
    (net (code "247") (name "unconnected-(U$13-PadP1.1_A1)") (class "Default")
      (node (ref "U$13") (pin "P1.1_A1") (pinfunction "P1.1_A1_P1.1_A1") (pintype "bidirectional"))
    )
    (net (code "248") (name "unconnected-(U$13-PadP1.2_A2)") (class "Default")
      (node (ref "U$13") (pin "P1.2_A2") (pinfunction "P1.2_A2_P1.2_A2") (pintype "bidirectional"))
    )
    (net (code "249") (name "unconnected-(U$13-PadP1.3_A3)") (class "Default")
      (node (ref "U$13") (pin "P1.3_A3") (pinfunction "P1.3_A3_P1.3_A3") (pintype "bidirectional"))
    )
    (net (code "250") (name "unconnected-(U$13-PadP1.4_A4)") (class "Default")
      (node (ref "U$13") (pin "P1.4_A4") (pinfunction "P1.4_A4_P1.4_A4") (pintype "bidirectional"))
    )
    (net (code "251") (name "unconnected-(U$13-PadP1.5_A5)") (class "Default")
      (node (ref "U$13") (pin "P1.5_A5") (pinfunction "P1.5_A5_P1.5_A5") (pintype "bidirectional"))
    )
    (net (code "252") (name "unconnected-(U$13-PadP2.2_GPIO{slash}PWM)") (class "Default")
      (node (ref "U$13") (pin "P2.2_GPIO/PWM") (pinfunction "P2.2_GPIO/PWM_P2.2_GPIO/PWM") (pintype "bidirectional"))
    )
    (net (code "253") (name "unconnected-(U$13-PadP2.7_SPI-CS3)") (class "Default")
      (node (ref "U$13") (pin "P2.7_SPI-CS3") (pinfunction "P2.7_SPI-CS3_P2.7_SPI-CS3") (pintype "bidirectional"))
    )
    (net (code "254") (name "unconnected-(U$13-PadP3.0_A12)") (class "Default")
      (node (ref "U$13") (pin "P3.0_A12") (pinfunction "P3.0_A12_P3.0_A12") (pintype "bidirectional"))
    )
    (net (code "255") (name "unconnected-(U$13-PadP3.1_A13)") (class "Default")
      (node (ref "U$13") (pin "P3.1_A13") (pinfunction "P3.1_A13_P3.1_A13") (pintype "bidirectional"))
    )
    (net (code "256") (name "unconnected-(U$13-PadP3.2_A14)") (class "Default")
      (node (ref "U$13") (pin "P3.2_A14") (pinfunction "P3.2_A14_P3.2_A14") (pintype "bidirectional"))
    )
    (net (code "257") (name "unconnected-(U$13-PadP3.3_A15)") (class "Default")
      (node (ref "U$13") (pin "P3.3_A15") (pinfunction "P3.3_A15_P3.3_A15") (pintype "bidirectional"))
    )
    (net (code "258") (name "unconnected-(U$13-PadP4.1_GPIO)") (class "Default")
      (node (ref "U$13") (pin "P4.1_GPIO") (pinfunction "P4.1_GPIO_P4.1_GPIO") (pintype "bidirectional"))
    )
    (net (code "259") (name "unconnected-(U$13-PadP4.2_GPIO)") (class "Default")
      (node (ref "U$13") (pin "P4.2_GPIO") (pinfunction "P4.2_GPIO_P4.2_GPIO") (pintype "bidirectional"))
    )
    (net (code "260") (name "unconnected-(U$13-PadP5.0_I2C-SDA-1)") (class "Default")
      (node (ref "U$13") (pin "P5.0_I2C-SDA-1") (pinfunction "P5.0_I2C-SDA-1_P5.0_I2C-SDA-1") (pintype "bidirectional"))
    )
    (net (code "261") (name "unconnected-(U$13-PadP5.1_I2C-SCL-1)") (class "Default")
      (node (ref "U$13") (pin "P5.1_I2C-SCL-1") (pinfunction "P5.1_I2C-SCL-1_P5.1_I2C-SCL-1") (pintype "bidirectional"))
    )
    (net (code "262") (name "unconnected-(U$13-PadP5.4_SPI-MOSI)") (class "Default")
      (node (ref "U$13") (pin "P5.4_SPI-MOSI") (pinfunction "P5.4_SPI-MOSI_P5.4_SPI-MOSI") (pintype "bidirectional"))
    )
    (net (code "263") (name "unconnected-(U$13-PadP5.5_SPI-MISO)") (class "Default")
      (node (ref "U$13") (pin "P5.5_SPI-MISO") (pinfunction "P5.5_SPI-MISO_P5.5_SPI-MISO") (pintype "bidirectional"))
    )
    (net (code "264") (name "unconnected-(U$13-PadP5.6_SPI-CLK)") (class "Default")
      (node (ref "U$13") (pin "P5.6_SPI-CLK") (pinfunction "P5.6_SPI-CLK_P5.6_SPI-CLK") (pintype "bidirectional"))
    )
    (net (code "265") (name "unconnected-(U$13-PadP7.0_I2C-SDA-2)") (class "Default")
      (node (ref "U$13") (pin "P7.0_I2C-SDA-2") (pinfunction "P7.0_I2C-SDA-2_P7.0_I2C-SDA-2") (pintype "bidirectional"))
    )
    (net (code "266") (name "unconnected-(U$13-PadP7.1_I2C-SCL-2)") (class "Default")
      (node (ref "U$13") (pin "P7.1_I2C-SCL-2") (pinfunction "P7.1_I2C-SCL-2_P7.1_I2C-SCL-2") (pintype "bidirectional"))
    )
  )
)
